# oresat-camera-card-v0.net
KiCad netlist of a schematic drawn in EAGLE
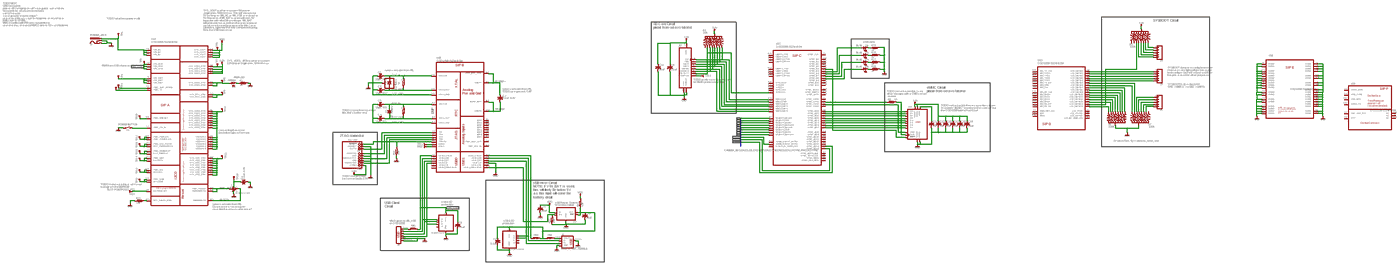
[diagram p0: schematic, sheet 1, overview]
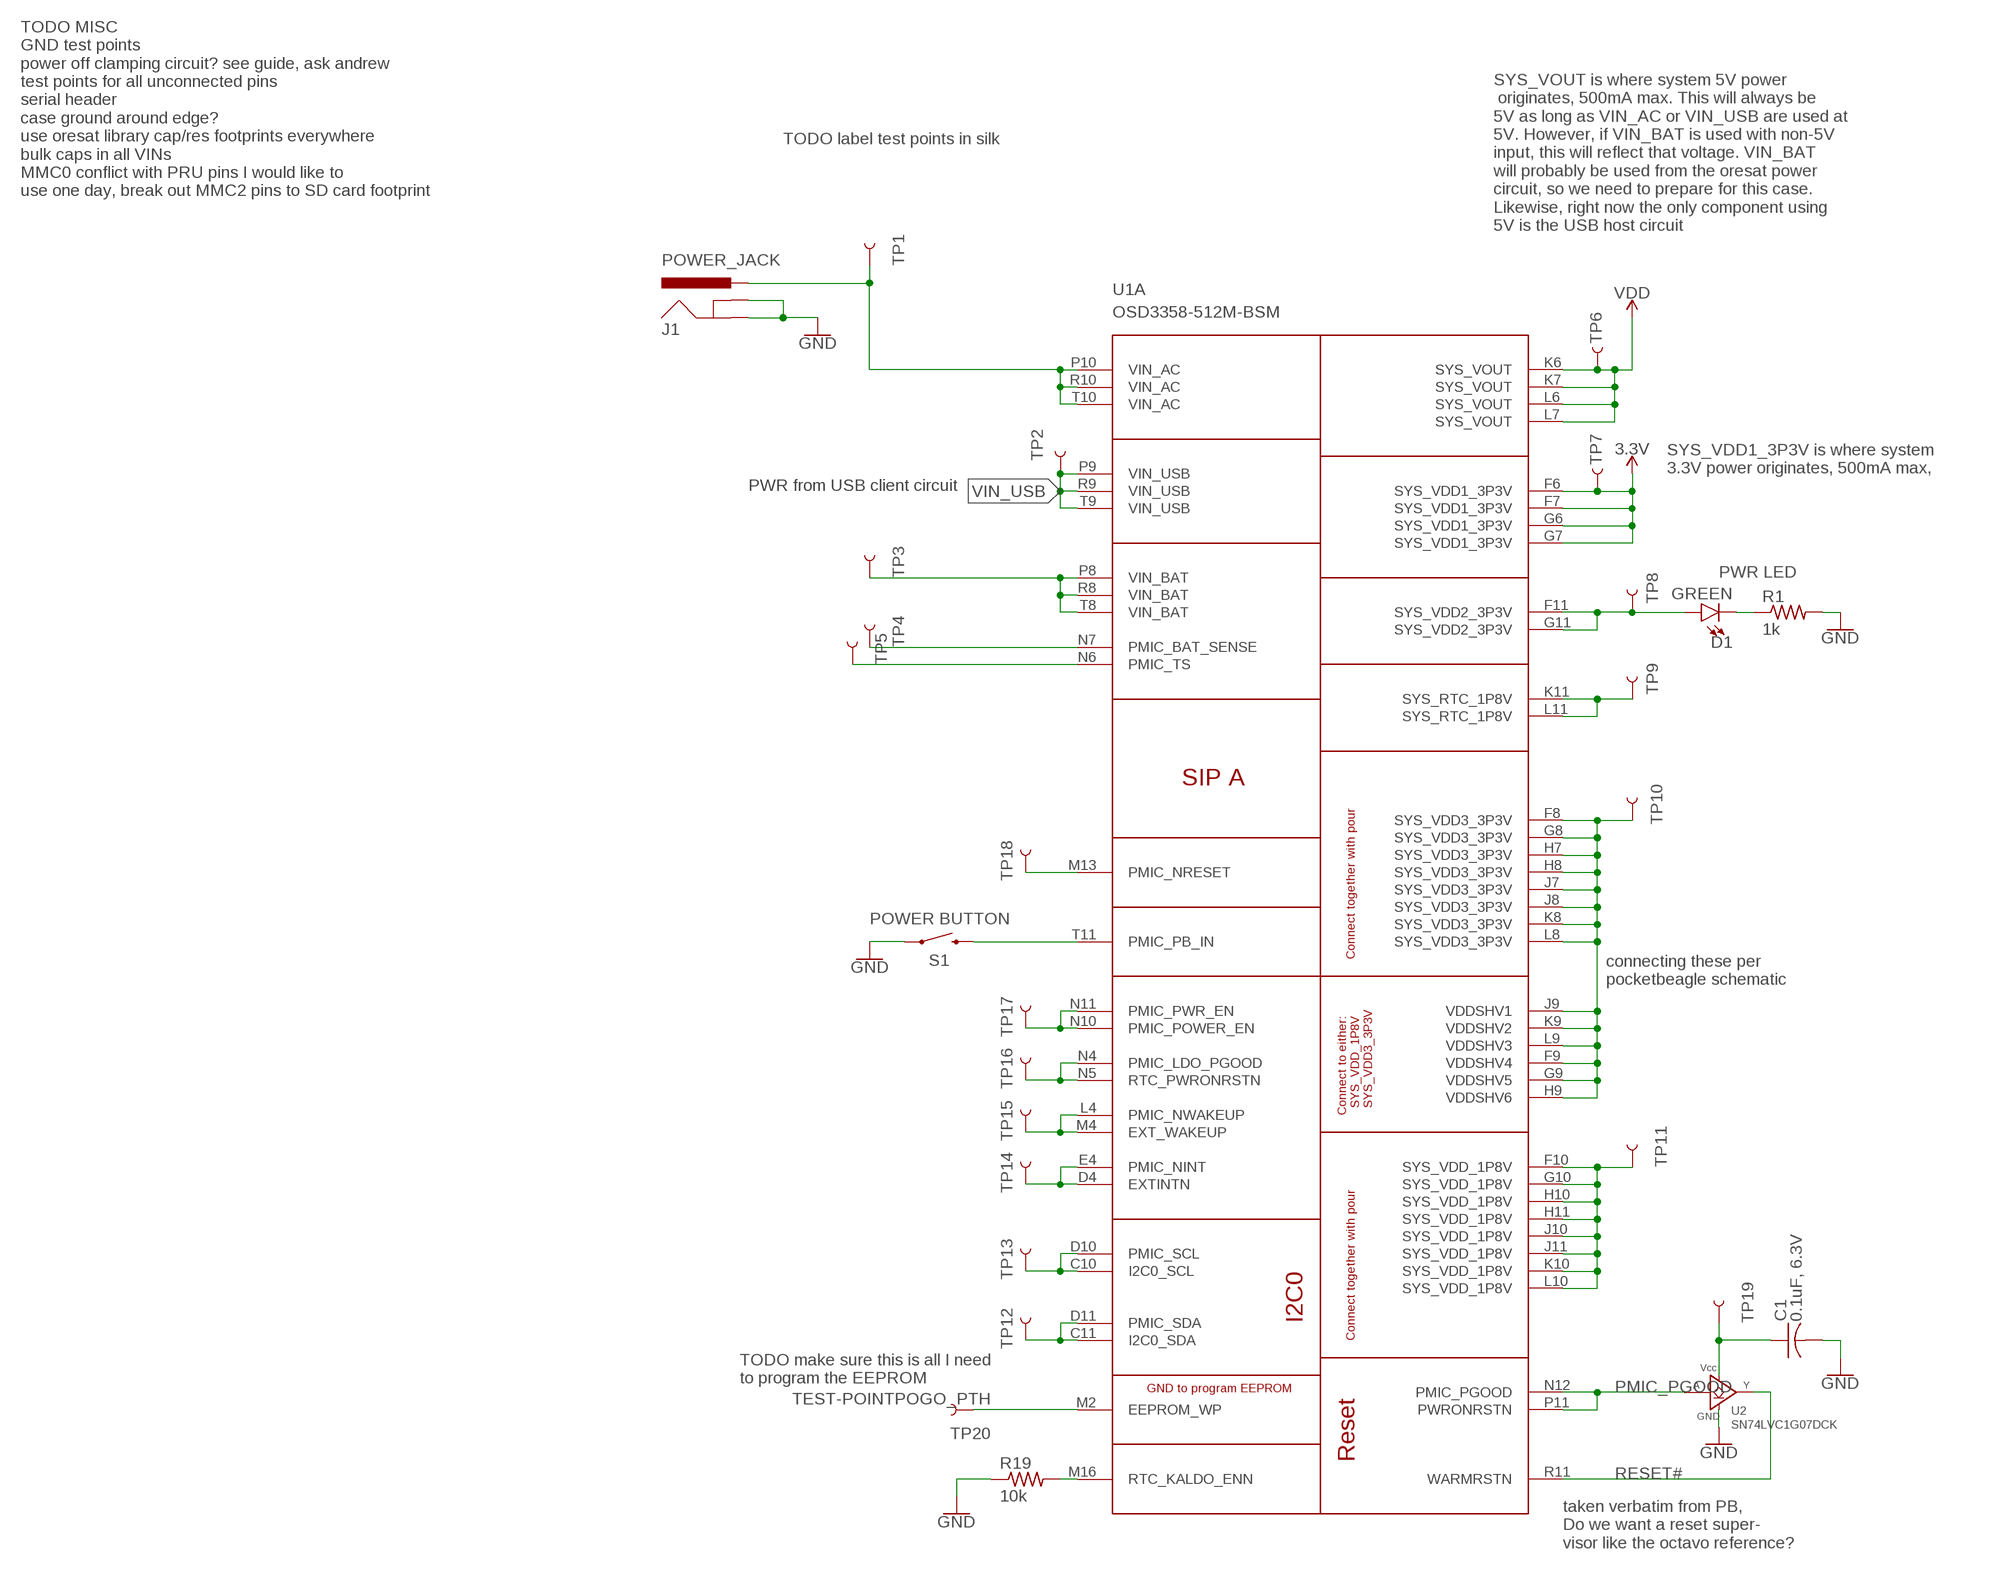
[diagram p1: schematic, sheet 1, part 1 of 4]
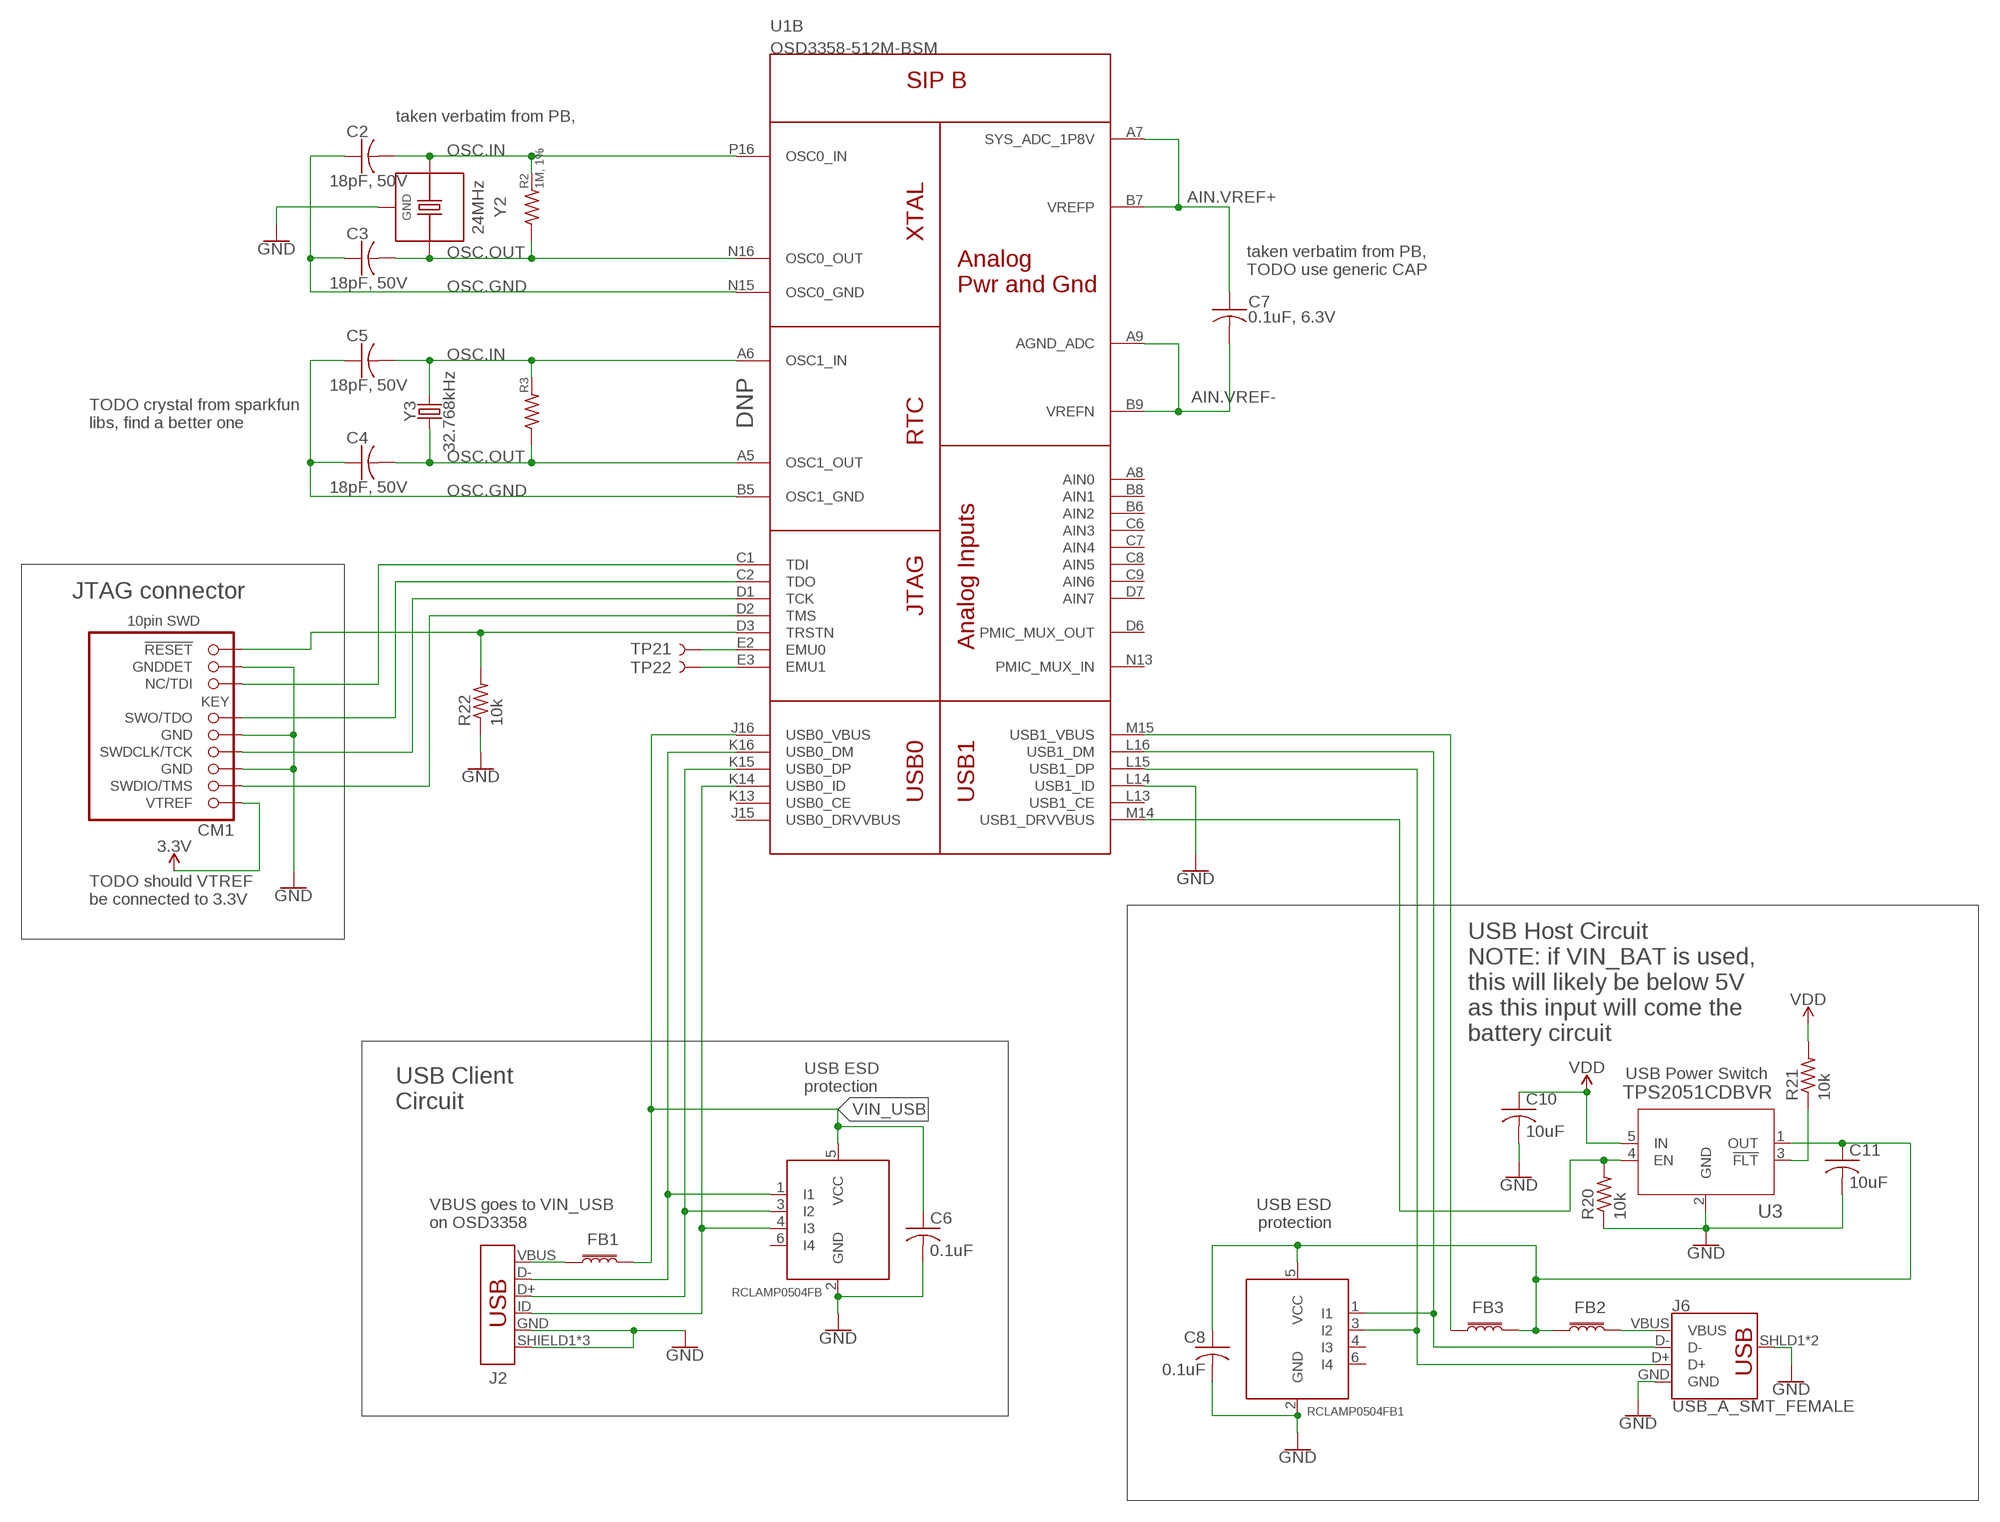
[diagram p2: schematic, sheet 1, part 2 of 4]
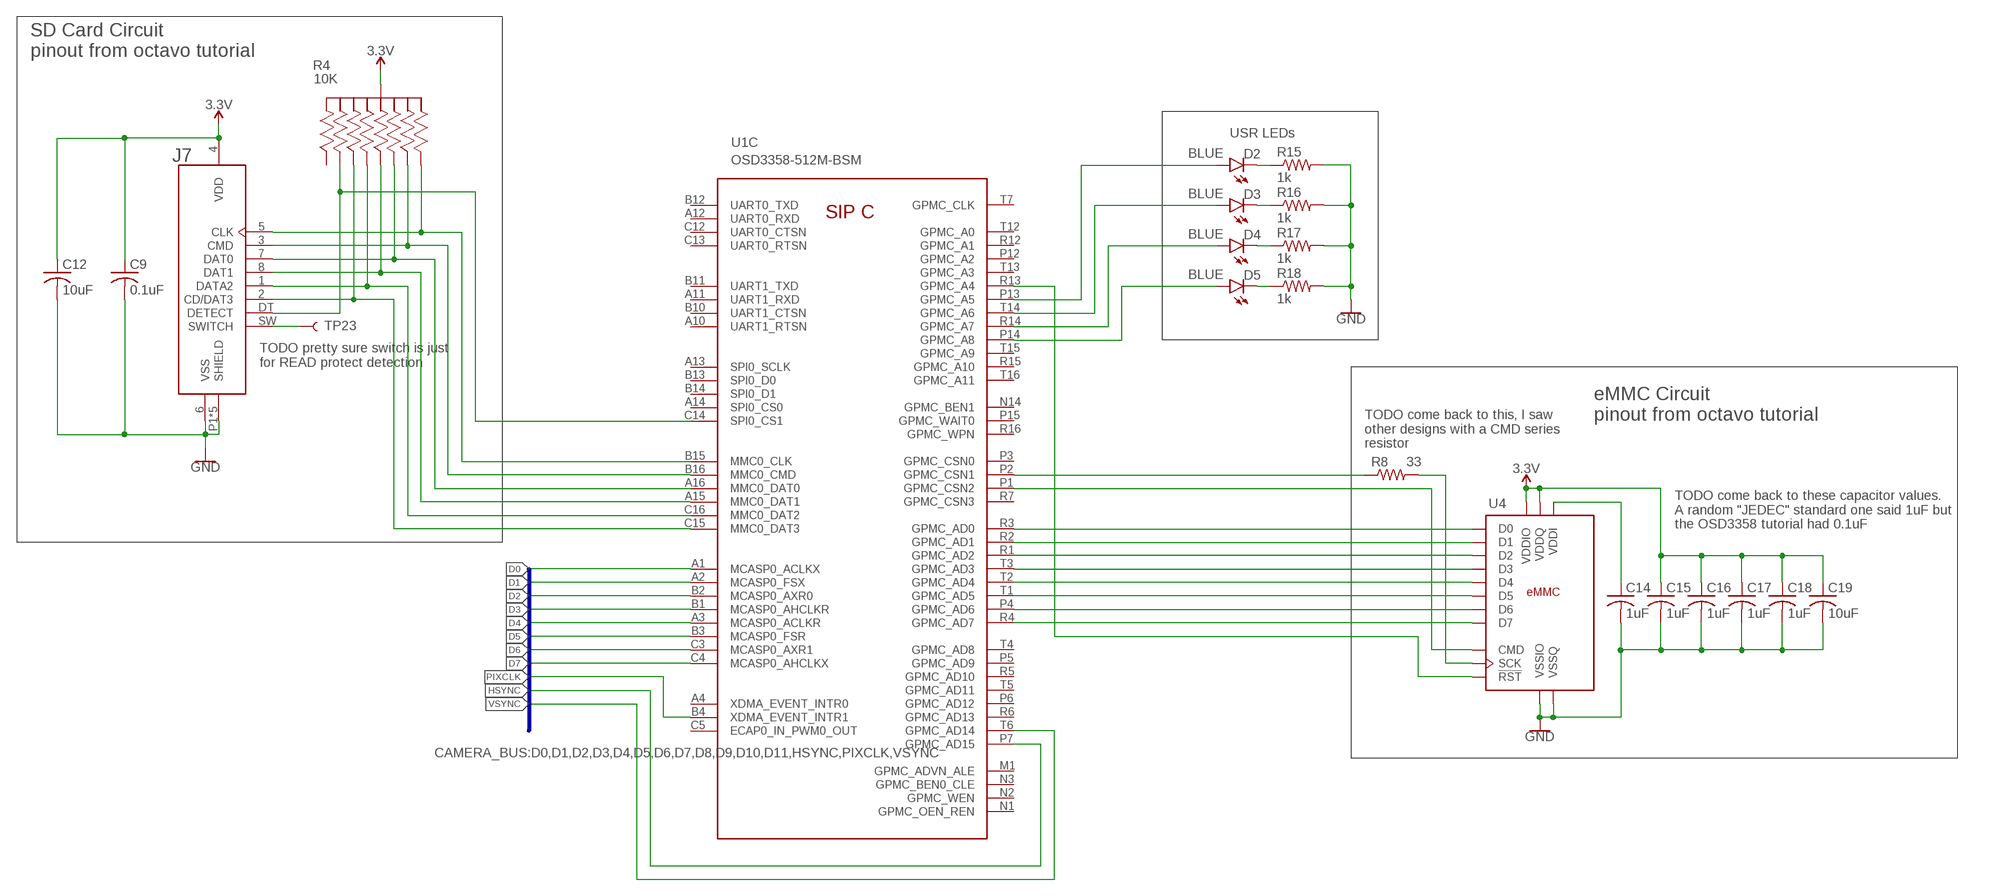
[diagram p3: schematic, sheet 1, part 3 of 4]
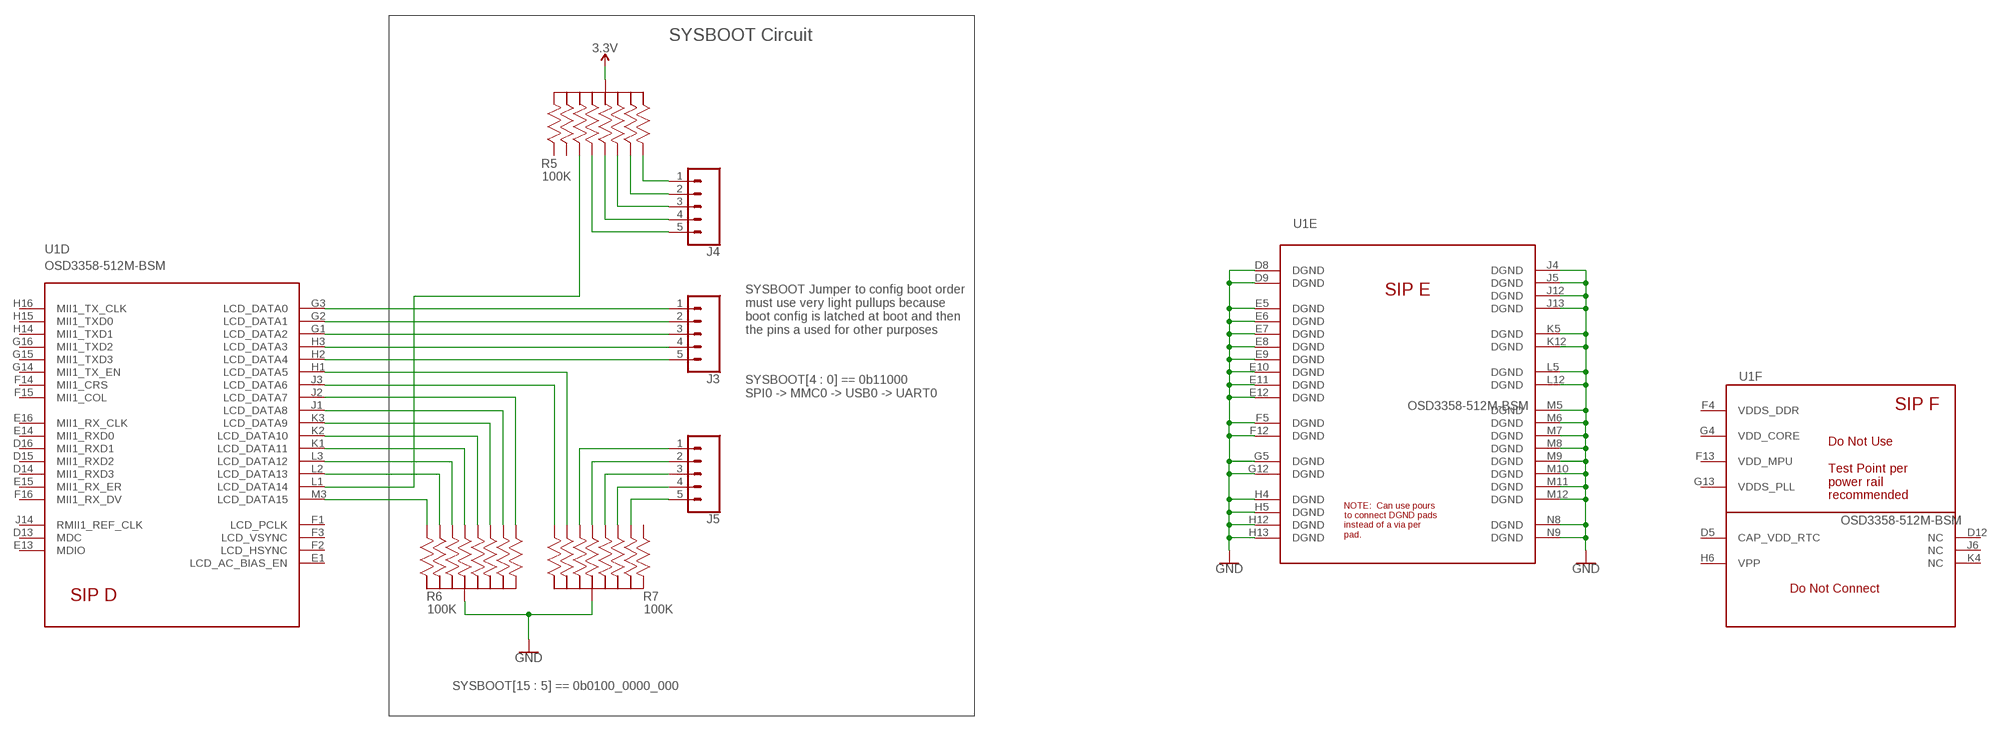
[diagram p4: schematic, sheet 1, part 4 of 4]

(export (version "E")
  (design (tool "Eeschema 10.0.6"))
  (components
    (comp (ref "C1")
      (value "0.1uF, 6.3V")
      (footprint "eagle-import:C0603")
      (libsource (lib "eagle-import") (part "C-USC0603"))
    )
    (comp (ref "C2")
      (value "18pF, 50V")
      (footprint "eagle-import:C0603")
      (libsource (lib "eagle-import") (part "C-USC0603"))
    )
    (comp (ref "C3")
      (value "18pF, 50V")
      (footprint "eagle-import:C0603")
      (libsource (lib "eagle-import") (part "C-USC0603"))
    )
    (comp (ref "C4")
      (value "18pF, 50V")
      (footprint "eagle-import:C0603")
      (libsource (lib "eagle-import") (part "C-USC0603"))
    )
    (comp (ref "C5")
      (value "18pF, 50V")
      (footprint "eagle-import:C0603")
      (libsource (lib "eagle-import") (part "C-USC0603"))
    )
    (comp (ref "C6")
      (value "0.1uF")
      (footprint "eagle-import:C0603")
      (libsource (lib "eagle-import") (part "C-USC0603"))
    )
    (comp (ref "C7")
      (value "0.1uF, 6.3V")
      (footprint "eagle-import:C0603")
      (libsource (lib "eagle-import") (part "C-USC0603"))
    )
    (comp (ref "C8")
      (value "0.1uF")
      (footprint "eagle-import:C0603")
      (libsource (lib "eagle-import") (part "C-USC0603"))
    )
    (comp (ref "C9")
      (value "0.1uF")
      (footprint "eagle-import:C0603")
      (libsource (lib "eagle-import") (part "C-USC0603"))
    )
    (comp (ref "C10")
      (value "10uF")
      (footprint "eagle-import:C0603")
      (libsource (lib "eagle-import") (part "C-USC0603"))
    )
    (comp (ref "C11")
      (value "10uF")
      (footprint "eagle-import:C0603")
      (libsource (lib "eagle-import") (part "C-USC0603"))
    )
    (comp (ref "C12")
      (value "10uF")
      (footprint "eagle-import:C0603")
      (libsource (lib "eagle-import") (part "C-USC0603"))
    )
    (comp (ref "C14")
      (value "1uF")
      (footprint "eagle-import:C0603")
      (libsource (lib "eagle-import") (part "C-USC0603"))
    )
    (comp (ref "C15")
      (value "1uF")
      (footprint "eagle-import:C0603")
      (libsource (lib "eagle-import") (part "C-USC0603"))
    )
    (comp (ref "C16")
      (value "1uF")
      (footprint "eagle-import:C0603")
      (libsource (lib "eagle-import") (part "C-USC0603"))
    )
    (comp (ref "C17")
      (value "1uF")
      (footprint "eagle-import:C0603")
      (libsource (lib "eagle-import") (part "C-USC0603"))
    )
    (comp (ref "C18")
      (value "1uF")
      (footprint "eagle-import:C0603")
      (libsource (lib "eagle-import") (part "C-USC0603"))
    )
    (comp (ref "C19")
      (value "10uF")
      (footprint "eagle-import:C0603")
      (libsource (lib "eagle-import") (part "C-USC0603"))
    )
    (comp (ref "CM1")
      (value "FTSH-105-XX-X-DV-K")
      (footprint "eagle-import:CON10_2X5_DUK_FTSH")
      (libsource (lib "eagle-import") (part "FTSH-105-XX-X-DV-K"))
    )
    (comp (ref "D1")
      (value "GREEN")
      (footprint "eagle-import:LED-0603")
      (libsource (lib "eagle-import") (part "LED-GREEN0603"))
    )
    (comp (ref "D2")
      (value "BLUE")
      (footprint "eagle-import:LED-0603")
      (libsource (lib "eagle-import") (part "LED-BLUE0603"))
    )
    (comp (ref "D3")
      (value "BLUE")
      (footprint "eagle-import:LED-0603")
      (libsource (lib "eagle-import") (part "LED-BLUE0603"))
    )
    (comp (ref "D4")
      (value "BLUE")
      (footprint "eagle-import:LED-0603")
      (libsource (lib "eagle-import") (part "LED-BLUE0603"))
    )
    (comp (ref "D5")
      (value "BLUE")
      (footprint "eagle-import:LED-0603")
      (libsource (lib "eagle-import") (part "LED-BLUE0603"))
    )
    (comp (ref "FB1")
      (value "30Ω/1.8A")
      (footprint "eagle-import:0603")
      (libsource (lib "eagle-import") (part "FERRITE_BEAD-0603"))
    )
    (comp (ref "FB2")
      (value "30Ω/1.8A")
      (footprint "eagle-import:0603")
      (libsource (lib "eagle-import") (part "FERRITE_BEAD-0603"))
    )
    (comp (ref "FB3")
      (value "30Ω/1.8A")
      (footprint "eagle-import:0603")
      (libsource (lib "eagle-import") (part "FERRITE_BEAD-0603"))
    )
    (comp (ref "J1")
      (value "POWER_JACK")
      (footprint "eagle-import:POWER_JACK_PTH")
      (libsource (lib "eagle-import") (part "POWER_JACK"))
    )
    (comp (ref "J2")
      (value "USB_MICRO-B_FEMALE-SMT")
      (footprint "eagle-import:USB-B-MICRO-SMD")
      (libsource (lib "eagle-import") (part "USB_MICRO-B_FEMALE-SMT"))
    )
    (comp (ref "J3")
      (value "CONN_05")
      (footprint "eagle-import:1X05")
      (libsource (lib "eagle-import") (part "CONN_05"))
    )
    (comp (ref "J4")
      (value "CONN_05")
      (footprint "eagle-import:1X05")
      (libsource (lib "eagle-import") (part "CONN_05"))
    )
    (comp (ref "J5")
      (value "CONN_05")
      (footprint "eagle-import:1X05")
      (libsource (lib "eagle-import") (part "CONN_05"))
    )
    (comp (ref "J6")
      (value "USB_A_SMT_FEMALE")
      (footprint "eagle-import:USB-A-S-SILK-FEMALE")
      (libsource (lib "eagle-import") (part "USB_A_SMT_FEMALE"))
    )
    (comp (ref "J7")
      (value "503182-1852")
      (footprint "eagle-import:MOLEX_503182-1852")
      (fields
        (field (name "DIGI-KEY_PART_NUMBER") "WM12834CT-ND")
        (field (name "MF") "Molex")
        (field (name "MP") "5031821852")
      )
      (libsource (lib "eagle-import") (part "503182-1852"))
    )
    (comp (ref "R1")
      (value "1k")
      (footprint "eagle-import:.0603-A")
      (libsource (lib "eagle-import") (part "R-US_0603-A"))
    )
    (comp (ref "R2")
      (value "1M, 1%")
      (footprint "eagle-import:.0603-A")
      (libsource (lib "eagle-import") (part "R-US_0603-A"))
    )
    (comp (ref "R3")
      (value "1M, 1%")
      (footprint "eagle-import:.0603-A")
      (libsource (lib "eagle-import") (part "R-US_0603-A"))
    )
    (comp (ref "R4")
      (value "10K")
      (footprint "eagle-import:ARRAY_EXBA-M")
      (fields (field (name "MANUFACTURER_PART_NUMBER") "EXBA10P391J"))
      (libsource (lib "eagle-import") (part "EXB-A10P391JC_ARRAY_EXBA-M"))
    )
    (comp (ref "R5")
      (value "100K")
      (footprint "eagle-import:ARRAY_EXBA-M")
      (fields (field (name "MANUFACTURER_PART_NUMBER") "EXBA10P391J"))
      (libsource (lib "eagle-import") (part "EXB-A10P391JC_ARRAY_EXBA-M"))
    )
    (comp (ref "R6")
      (value "100K")
      (footprint "eagle-import:ARRAY_EXBA-M")
      (fields (field (name "MANUFACTURER_PART_NUMBER") "EXBA10P391J"))
      (libsource (lib "eagle-import") (part "EXB-A10P391JC_ARRAY_EXBA-M"))
    )
    (comp (ref "R7")
      (value "100K")
      (footprint "eagle-import:ARRAY_EXBA-M")
      (fields (field (name "MANUFACTURER_PART_NUMBER") "EXBA10P391J"))
      (libsource (lib "eagle-import") (part "EXB-A10P391JC_ARRAY_EXBA-M"))
    )
    (comp (ref "R8")
      (value "33")
      (footprint "eagle-import:.0603-A")
      (libsource (lib "eagle-import") (part "R-US_0603-A"))
    )
    (comp (ref "R15")
      (value "1k")
      (footprint "eagle-import:.0603-A")
      (libsource (lib "eagle-import") (part "R-US_0603-A"))
    )
    (comp (ref "R16")
      (value "1k")
      (footprint "eagle-import:.0603-A")
      (libsource (lib "eagle-import") (part "R-US_0603-A"))
    )
    (comp (ref "R17")
      (value "1k")
      (footprint "eagle-import:.0603-A")
      (libsource (lib "eagle-import") (part "R-US_0603-A"))
    )
    (comp (ref "R18")
      (value "1k")
      (footprint "eagle-import:.0603-A")
      (libsource (lib "eagle-import") (part "R-US_0603-A"))
    )
    (comp (ref "R19")
      (value "10k")
      (footprint "eagle-import:.0603-A")
      (libsource (lib "eagle-import") (part "R-US_0603-A"))
    )
    (comp (ref "R20")
      (value "10k")
      (footprint "eagle-import:.0603-A")
      (libsource (lib "eagle-import") (part "R-US_0603-A"))
    )
    (comp (ref "R21")
      (value "10k")
      (footprint "eagle-import:.0603-A")
      (libsource (lib "eagle-import") (part "R-US_0603-A"))
    )
    (comp (ref "R22")
      (value "10k")
      (footprint "eagle-import:.0603-A")
      (libsource (lib "eagle-import") (part "R-US_0603-A"))
    )
    (comp (ref "RCLAMP0504FB")
      (value "RCLAMP0504FB")
      (footprint "eagle-import:SC70-6")
      (libsource (lib "eagle-import") (part "RCLAMP0504FB"))
    )
    (comp (ref "RCLAMP0504FB1")
      (value "RCLAMP0504FB")
      (footprint "eagle-import:SC70-6")
      (libsource (lib "eagle-import") (part "RCLAMP0504FB"))
    )
    (comp (ref "S1")
      (value "MOMENTARY-SWITCH-SPST-SMD-4.6X2.8MM")
      (footprint "eagle-import:TACTILE_SWITCH_SMD_4.6X2.8MM")
      (libsource (lib "eagle-import") (part "MOMENTARY-SWITCH-SPST-SMD-4.6X2.8MM"))
    )
    (comp (ref "TP1")
      (value "TEST-POINT3X4")
      (footprint "eagle-import:PAD.03X.04")
      (libsource (lib "eagle-import") (part "TEST-POINT3X4"))
    )
    (comp (ref "TP2")
      (value "TEST-POINT3X4")
      (footprint "eagle-import:PAD.03X.04")
      (libsource (lib "eagle-import") (part "TEST-POINT3X4"))
    )
    (comp (ref "TP3")
      (value "TEST-POINT3X4")
      (footprint "eagle-import:PAD.03X.04")
      (libsource (lib "eagle-import") (part "TEST-POINT3X4"))
    )
    (comp (ref "TP4")
      (value "TEST-POINT3X4")
      (footprint "eagle-import:PAD.03X.04")
      (libsource (lib "eagle-import") (part "TEST-POINT3X4"))
    )
    (comp (ref "TP5")
      (value "TEST-POINT3X4")
      (footprint "eagle-import:PAD.03X.04")
      (libsource (lib "eagle-import") (part "TEST-POINT3X4"))
    )
    (comp (ref "TP6")
      (value "TEST-POINT3X4")
      (footprint "eagle-import:PAD.03X.04")
      (libsource (lib "eagle-import") (part "TEST-POINT3X4"))
    )
    (comp (ref "TP7")
      (value "TEST-POINT3X4")
      (footprint "eagle-import:PAD.03X.04")
      (libsource (lib "eagle-import") (part "TEST-POINT3X4"))
    )
    (comp (ref "TP8")
      (value "TEST-POINT3X4")
      (footprint "eagle-import:PAD.03X.04")
      (libsource (lib "eagle-import") (part "TEST-POINT3X4"))
    )
    (comp (ref "TP9")
      (value "TEST-POINT3X4")
      (footprint "eagle-import:PAD.03X.04")
      (libsource (lib "eagle-import") (part "TEST-POINT3X4"))
    )
    (comp (ref "TP10")
      (value "TEST-POINT3X4")
      (footprint "eagle-import:PAD.03X.04")
      (libsource (lib "eagle-import") (part "TEST-POINT3X4"))
    )
    (comp (ref "TP11")
      (value "TEST-POINT3X4")
      (footprint "eagle-import:PAD.03X.04")
      (libsource (lib "eagle-import") (part "TEST-POINT3X4"))
    )
    (comp (ref "TP12")
      (value "TEST-POINT3X4")
      (footprint "eagle-import:PAD.03X.04")
      (libsource (lib "eagle-import") (part "TEST-POINT3X4"))
    )
    (comp (ref "TP13")
      (value "TEST-POINT3X4")
      (footprint "eagle-import:PAD.03X.04")
      (libsource (lib "eagle-import") (part "TEST-POINT3X4"))
    )
    (comp (ref "TP14")
      (value "TEST-POINT3X4")
      (footprint "eagle-import:PAD.03X.04")
      (libsource (lib "eagle-import") (part "TEST-POINT3X4"))
    )
    (comp (ref "TP15")
      (value "TEST-POINT3X4")
      (footprint "eagle-import:PAD.03X.04")
      (libsource (lib "eagle-import") (part "TEST-POINT3X4"))
    )
    (comp (ref "TP16")
      (value "TEST-POINT3X4")
      (footprint "eagle-import:PAD.03X.04")
      (libsource (lib "eagle-import") (part "TEST-POINT3X4"))
    )
    (comp (ref "TP17")
      (value "TEST-POINT3X4")
      (footprint "eagle-import:PAD.03X.04")
      (libsource (lib "eagle-import") (part "TEST-POINT3X4"))
    )
    (comp (ref "TP18")
      (value "TEST-POINT3X4")
      (footprint "eagle-import:PAD.03X.04")
      (libsource (lib "eagle-import") (part "TEST-POINT3X4"))
    )
    (comp (ref "TP19")
      (value "TEST-POINT3X4")
      (footprint "eagle-import:PAD.03X.04")
      (libsource (lib "eagle-import") (part "TEST-POINT3X4"))
    )
    (comp (ref "TP20")
      (value "TEST-POINTPOGO_PTH")
      (footprint "eagle-import:1X01_NO_SILK")
      (libsource (lib "eagle-import") (part "TEST-POINTPOGO_PTH"))
    )
    (comp (ref "TP21")
      (value "TEST-POINT3X4")
      (footprint "eagle-import:PAD.03X.04")
      (libsource (lib "eagle-import") (part "TEST-POINT3X4"))
    )
    (comp (ref "TP22")
      (value "TEST-POINT3X4")
      (footprint "eagle-import:PAD.03X.04")
      (libsource (lib "eagle-import") (part "TEST-POINT3X4"))
    )
    (comp (ref "TP23")
      (value "TEST-POINT3X4")
      (footprint "eagle-import:PAD.03X.04")
      (libsource (lib "eagle-import") (part "TEST-POINT3X4"))
    )
    (comp (ref "U1")
      (value "OSD3358-512M-BSM")
      (footprint "eagle-import:OSD335X-BGA-256")
      (fields (field (name "DIGI-KEY_PART_NUMBER") "1676-1002-ND") (field (name "MF") "Octavo Systems"))
      (libsource (lib "eagle-import") (part "OSD3358-512M-BSM"))
    )
    (comp (ref "U2")
      (value "SN74LVC1G07DCK")
      (footprint "eagle-import:SC70(TI-DCK)")
      (libsource (lib "eagle-import") (part "SN74LVC1G07DCK"))
    )
    (comp (ref "U3")
      (value "TPS2051CDBVR")
      (footprint "eagle-import:DBV5")
      (libsource (lib "eagle-import") (part "TPS2051CDBVR"))
    )
    (comp (ref "U4")
      (value "EMMC+RESET-BA")
      (footprint "eagle-import:BGA-153(11.5X13)(EMMC-BA)")
      (libsource (lib "eagle-import") (part "EMMC+RESET-BA"))
    )
    (comp (ref "Y2")
      (value "24MHz")
      (footprint "eagle-import:5X3.2-4SMD")
      (libsource (lib "eagle-import") (part "ECS-240-12-30BQ-AEN-TR"))
    )
    (comp (ref "Y3")
      (value "32.768kHz")
      (footprint "eagle-import:CRYSTAL-SMD-3.2X1.5MM")
      (libsource (lib "eagle-import") (part "CRYSTAL-32.768KHZSMD-3.2X1.5"))
    )
  )
  (nets
    (net (code "6") (name "/AIN.VREF+") (class "Default")
      (node (ref "C7") (pin "1") (pinfunction "1_1") (pintype "passive"))
      (node (ref "U1") (pin "A7") (pinfunction "SYS_ADC_1P8V_A7") (pintype "bidirectional"))
      (node (ref "U1") (pin "B7") (pinfunction "VREFP_B7") (pintype "bidirectional"))
    )
    (net (code "7") (name "/AIN.VREF-") (class "Default")
      (node (ref "C7") (pin "2") (pinfunction "2_2") (pintype "passive"))
      (node (ref "U1") (pin "A9") (pinfunction "AGND_ADC_A9") (pintype "bidirectional"))
      (node (ref "U1") (pin "B9") (pinfunction "VREFN_B9") (pintype "bidirectional"))
    )
    (net (code "8") (name "/OSC.GND") (class "Default")
      (node (ref "C2") (pin "1") (pinfunction "1_1") (pintype "passive"))
      (node (ref "C3") (pin "1") (pinfunction "1_1") (pintype "passive"))
      (node (ref "C4") (pin "1") (pinfunction "1_1") (pintype "passive"))
      (node (ref "C5") (pin "1") (pinfunction "1_1") (pintype "passive"))
      (node (ref "U1") (pin "B5") (pinfunction "OSC1_GND_B5") (pintype "bidirectional"))
      (node (ref "U1") (pin "N15") (pinfunction "OSC0_GND_N15") (pintype "bidirectional"))
    )
    (net (code "9") (name "/OSC.IN") (class "Default")
      (node (ref "C2") (pin "2") (pinfunction "2_2") (pintype "passive"))
      (node (ref "C5") (pin "2") (pinfunction "2_2") (pintype "passive"))
      (node (ref "R2") (pin "2") (pinfunction "2_2") (pintype "passive"))
      (node (ref "R3") (pin "2") (pinfunction "2_2") (pintype "passive"))
      (node (ref "U1") (pin "A6") (pinfunction "OSC1_IN_A6") (pintype "bidirectional"))
      (node (ref "U1") (pin "P16") (pinfunction "OSC0_IN_P16") (pintype "bidirectional"))
      (node (ref "Y2") (pin "1") (pinfunction "X1_1") (pintype "passive"))
      (node (ref "Y3") (pin "P$2") (pinfunction "2_P$2") (pintype "passive"))
    )
    (net (code "10") (name "/OSC.OUT") (class "Default")
      (node (ref "C3") (pin "2") (pinfunction "2_2") (pintype "passive"))
      (node (ref "C4") (pin "2") (pinfunction "2_2") (pintype "passive"))
      (node (ref "R2") (pin "1") (pinfunction "1_1") (pintype "passive"))
      (node (ref "R3") (pin "1") (pinfunction "1_1") (pintype "passive"))
      (node (ref "U1") (pin "A5") (pinfunction "OSC1_OUT_A5") (pintype "bidirectional"))
      (node (ref "U1") (pin "N16") (pinfunction "OSC0_OUT_N16") (pintype "bidirectional"))
      (node (ref "Y2") (pin "3") (pinfunction "X2_3") (pintype "passive"))
      (node (ref "Y3") (pin "P$1") (pinfunction "1_P$1") (pintype "passive"))
    )
    (net (code "11") (name "/PMIC_PGOOD") (class "Default")
      (node (ref "U1") (pin "N12") (pinfunction "PMIC_PGOOD_N12") (pintype "output"))
      (node (ref "U1") (pin "P11") (pinfunction "PWRONRSTN_P11") (pintype "bidirectional"))
      (node (ref "U2") (pin "2") (pinfunction "A_2") (pintype "bidirectional"))
    )
    (net (code "12") (name "/RESET#") (class "Default")
      (node (ref "U1") (pin "R11") (pinfunction "WARMRSTN_R11") (pintype "bidirectional"))
      (node (ref "U2") (pin "4") (pinfunction "Y_4") (pintype "bidirectional"))
    )
    (net (code "14") (name "3.3V") (class "Default")
      (node (ref "C12") (pin "1") (pinfunction "1_1") (pintype "passive"))
      (node (ref "C15") (pin "1") (pinfunction "1_1") (pintype "passive"))
      (node (ref "C16") (pin "1") (pinfunction "1_1") (pintype "passive"))
      (node (ref "C17") (pin "1") (pinfunction "1_1") (pintype "passive"))
      (node (ref "C18") (pin "1") (pinfunction "1_1") (pintype "passive"))
      (node (ref "C19") (pin "1") (pinfunction "1_1") (pintype "passive"))
      (node (ref "C9") (pin "1") (pinfunction "1_1") (pintype "passive"))
      (node (ref "CM1") (pin "1") (pinfunction "VTREF_1") (pintype "passive"))
      (node (ref "J7") (pin "4") (pinfunction "VDD_4") (pintype "power_in"))
      (node (ref "R4") (pin "10") (pinfunction "55_10") (pintype "passive"))
      (node (ref "R4") (pin "5") (pinfunction "55_5") (pintype "passive"))
      (node (ref "R5") (pin "10") (pinfunction "55_10") (pintype "passive"))
      (node (ref "R5") (pin "5") (pinfunction "55_5") (pintype "passive"))
      (node (ref "TP7") (pin "P$1") (pinfunction "1_P$1") (pintype "bidirectional"))
      (node (ref "U1") (pin "F6") (pinfunction "SYS_VDD1_3P3V_F6") (pintype "power_in"))
      (node (ref "U1") (pin "F7") (pinfunction "SYS_VDD1_3P3V_F7") (pintype "power_in"))
      (node (ref "U1") (pin "G6") (pinfunction "SYS_VDD1_3P3V_G6") (pintype "power_in"))
      (node (ref "U1") (pin "G7") (pinfunction "SYS_VDD1_3P3V_G7") (pintype "power_in"))
      (node (ref "U4") (pin "C6") (pinfunction "VDDQ_C6") (pintype "power_in"))
      (node (ref "U4") (pin "E6") (pinfunction "VDDIO_E6") (pintype "power_in"))
      (node (ref "U4") (pin "F5") (pinfunction "VDDIO_F5") (pintype "power_in"))
      (node (ref "U4") (pin "J10") (pinfunction "VDDIO_J10") (pintype "power_in"))
      (node (ref "U4") (pin "K9") (pinfunction "VDDIO_K9") (pintype "power_in"))
      (node (ref "U4") (pin "M4") (pinfunction "VDDQ_M4") (pintype "power_in"))
      (node (ref "U4") (pin "N4") (pinfunction "VDDQ_N4") (pintype "power_in"))
      (node (ref "U4") (pin "P3") (pinfunction "VDDQ_P3") (pintype "power_in"))
      (node (ref "U4") (pin "P5") (pinfunction "VDDQ_P5") (pintype "power_in"))
    )
    (net (code "15") (name "D0") (class "Default")
      (node (ref "U1") (pin "A1") (pinfunction "MCASP0_ACLKX_A1") (pintype "bidirectional"))
    )
    (net (code "16") (name "D1") (class "Default")
      (node (ref "U1") (pin "A2") (pinfunction "MCASP0_FSX_A2") (pintype "bidirectional"))
    )
    (net (code "17") (name "D2") (class "Default")
      (node (ref "U1") (pin "B2") (pinfunction "MCASP0_AXR0_B2") (pintype "bidirectional"))
    )
    (net (code "18") (name "D3") (class "Default")
      (node (ref "U1") (pin "B1") (pinfunction "MCASP0_AHCLKR_B1") (pintype "bidirectional"))
    )
    (net (code "19") (name "D4") (class "Default")
      (node (ref "U1") (pin "A3") (pinfunction "MCASP0_ACLKR_A3") (pintype "bidirectional"))
    )
    (net (code "20") (name "D5") (class "Default")
      (node (ref "U1") (pin "B3") (pinfunction "MCASP0_FSR_B3") (pintype "bidirectional"))
    )
    (net (code "21") (name "D6") (class "Default")
      (node (ref "U1") (pin "C3") (pinfunction "MCASP0_AXR1_C3") (pintype "bidirectional"))
    )
    (net (code "22") (name "D7") (class "Default")
      (node (ref "U1") (pin "C4") (pinfunction "MCASP0_AHCLKX_C4") (pintype "bidirectional"))
    )
    (net (code "23") (name "GND") (class "Default")
      (node (ref "C1") (pin "2") (pinfunction "2_2") (pintype "passive"))
      (node (ref "C10") (pin "2") (pinfunction "2_2") (pintype "passive"))
      (node (ref "C11") (pin "2") (pinfunction "2_2") (pintype "passive"))
      (node (ref "C12") (pin "2") (pinfunction "2_2") (pintype "passive"))
      (node (ref "C14") (pin "2") (pinfunction "2_2") (pintype "passive"))
      (node (ref "C15") (pin "2") (pinfunction "2_2") (pintype "passive"))
      (node (ref "C16") (pin "2") (pinfunction "2_2") (pintype "passive"))
      (node (ref "C17") (pin "2") (pinfunction "2_2") (pintype "passive"))
      (node (ref "C18") (pin "2") (pinfunction "2_2") (pintype "passive"))
      (node (ref "C19") (pin "2") (pinfunction "2_2") (pintype "passive"))
      (node (ref "C6") (pin "2") (pinfunction "2_2") (pintype "passive"))
      (node (ref "C8") (pin "2") (pinfunction "2_2") (pintype "passive"))
      (node (ref "C9") (pin "2") (pinfunction "2_2") (pintype "passive"))
      (node (ref "CM1") (pin "3") (pinfunction "GND_3") (pintype "passive"))
      (node (ref "CM1") (pin "5") (pinfunction "GND_5") (pintype "passive"))
      (node (ref "CM1") (pin "9") (pinfunction "GNDDET_9") (pintype "passive"))
      (node (ref "J1") (pin "GND") (pinfunction "GND_GND") (pintype "bidirectional"))
      (node (ref "J1") (pin "GNDBREAK") (pinfunction "GNDBREAK_GNDBREAK") (pintype "bidirectional"))
      (node (ref "J2") (pin "GND") (pinfunction "GND_GND") (pintype "power_in"))
      (node (ref "J2") (pin "SHIELD1") (pinfunction "SHIELD_SHIELD1") (pintype "bidirectional"))
      (node (ref "J2") (pin "SHIELD2") (pinfunction "SHIELD_SHIELD2") (pintype "bidirectional"))
      (node (ref "J2") (pin "SHIELD3") (pinfunction "SHIELD_SHIELD3") (pintype "bidirectional"))
      (node (ref "J6") (pin "GND") (pinfunction "GND_GND") (pintype "power_in"))
      (node (ref "J6") (pin "SHLD1") (pinfunction "SHIELD_SHLD1") (pintype "bidirectional"))
      (node (ref "J6") (pin "SHLD2") (pinfunction "SHIELD_SHLD2") (pintype "bidirectional"))
      (node (ref "J7") (pin "6") (pinfunction "VSS_6") (pintype "power_in"))
      (node (ref "J7") (pin "P1") (pinfunction "SHIELD_P1") (pintype "passive"))
      (node (ref "J7") (pin "P2") (pinfunction "SHIELD_P2") (pintype "passive"))
      (node (ref "J7") (pin "P3") (pinfunction "SHIELD_P3") (pintype "passive"))
      (node (ref "J7") (pin "P4") (pinfunction "SHIELD_P4") (pintype "passive"))
      (node (ref "J7") (pin "P5") (pinfunction "SHIELD_P5") (pintype "passive"))
      (node (ref "R1") (pin "2") (pinfunction "2_2") (pintype "passive"))
      (node (ref "R15") (pin "2") (pinfunction "2_2") (pintype "passive"))
      (node (ref "R16") (pin "2") (pinfunction "2_2") (pintype "passive"))
      (node (ref "R17") (pin "2") (pinfunction "2_2") (pintype "passive"))
      (node (ref "R18") (pin "2") (pinfunction "2_2") (pintype "passive"))
      (node (ref "R19") (pin "1") (pinfunction "1_1") (pintype "passive"))
      (node (ref "R20") (pin "1") (pinfunction "1_1") (pintype "passive"))
      (node (ref "R22") (pin "1") (pinfunction "1_1") (pintype "passive"))
      (node (ref "R6") (pin "10") (pinfunction "55_10") (pintype "passive"))
      (node (ref "R6") (pin "5") (pinfunction "55_5") (pintype "passive"))
      (node (ref "R7") (pin "10") (pinfunction "55_10") (pintype "passive"))
      (node (ref "R7") (pin "5") (pinfunction "55_5") (pintype "passive"))
      (node (ref "RCLAMP0504FB") (pin "2") (pinfunction "GND_2") (pintype "power_in"))
      (node (ref "RCLAMP0504FB1") (pin "2") (pinfunction "GND_2") (pintype "power_in"))
      (node (ref "S1") (pin "1") (pinfunction "1_1") (pintype "passive"))
      (node (ref "S1") (pin "2") (pinfunction "1_2") (pintype "passive"))
      (node (ref "U1") (pin "D8") (pinfunction "DGND_D8") (pintype "bidirectional"))
      (node (ref "U1") (pin "D9") (pinfunction "DGND_D9") (pintype "bidirectional"))
      (node (ref "U1") (pin "E10") (pinfunction "DGND_E10") (pintype "bidirectional"))
      (node (ref "U1") (pin "E11") (pinfunction "DGND_E11") (pintype "bidirectional"))
      (node (ref "U1") (pin "E12") (pinfunction "DGND_E12") (pintype "bidirectional"))
      (node (ref "U1") (pin "E5") (pinfunction "DGND_E5") (pintype "bidirectional"))
      (node (ref "U1") (pin "E6") (pinfunction "DGND_E6") (pintype "bidirectional"))
      (node (ref "U1") (pin "E7") (pinfunction "DGND_E7") (pintype "bidirectional"))
      (node (ref "U1") (pin "E8") (pinfunction "DGND_E8") (pintype "bidirectional"))
      (node (ref "U1") (pin "E9") (pinfunction "DGND_E9") (pintype "bidirectional"))
      (node (ref "U1") (pin "F12") (pinfunction "DGND_F12") (pintype "bidirectional"))
      (node (ref "U1") (pin "F5") (pinfunction "DGND_F5") (pintype "bidirectional"))
      (node (ref "U1") (pin "G12") (pinfunction "DGND_G12") (pintype "bidirectional"))
      (node (ref "U1") (pin "G5") (pinfunction "DGND_G5") (pintype "bidirectional"))
      (node (ref "U1") (pin "H12") (pinfunction "DGND_H12") (pintype "bidirectional"))
      (node (ref "U1") (pin "H13") (pinfunction "DGND_H13") (pintype "bidirectional"))
      (node (ref "U1") (pin "H4") (pinfunction "DGND_H4") (pintype "bidirectional"))
      (node (ref "U1") (pin "H5") (pinfunction "DGND_H5") (pintype "bidirectional"))
      (node (ref "U1") (pin "J12") (pinfunction "DGND_J12") (pintype "bidirectional"))
      (node (ref "U1") (pin "J13") (pinfunction "DGND_J13") (pintype "bidirectional"))
      (node (ref "U1") (pin "J4") (pinfunction "DGND_J4") (pintype "bidirectional"))
      (node (ref "U1") (pin "J5") (pinfunction "DGND_J5") (pintype "bidirectional"))
      (node (ref "U1") (pin "K12") (pinfunction "DGND_K12") (pintype "bidirectional"))
      (node (ref "U1") (pin "K5") (pinfunction "DGND_K5") (pintype "bidirectional"))
      (node (ref "U1") (pin "L12") (pinfunction "DGND_L12") (pintype "bidirectional"))
      (node (ref "U1") (pin "L14") (pinfunction "USB1_ID_L14") (pintype "bidirectional"))
      (node (ref "U1") (pin "L5") (pinfunction "DGND_L5") (pintype "bidirectional"))
      (node (ref "U1") (pin "M10") (pinfunction "DGND_M10") (pintype "bidirectional"))
      (node (ref "U1") (pin "M11") (pinfunction "DGND_M11") (pintype "bidirectional"))
      (node (ref "U1") (pin "M12") (pinfunction "DGND_M12") (pintype "bidirectional"))
      (node (ref "U1") (pin "M5") (pinfunction "DGND_M5") (pintype "bidirectional"))
      (node (ref "U1") (pin "M6") (pinfunction "DGND_M6") (pintype "bidirectional"))
      (node (ref "U1") (pin "M7") (pinfunction "DGND_M7") (pintype "bidirectional"))
      (node (ref "U1") (pin "M8") (pinfunction "DGND_M8") (pintype "bidirectional"))
      (node (ref "U1") (pin "M9") (pinfunction "DGND_M9") (pintype "bidirectional"))
      (node (ref "U1") (pin "N8") (pinfunction "DGND_N8") (pintype "bidirectional"))
      (node (ref "U1") (pin "N9") (pinfunction "DGND_N9") (pintype "bidirectional"))
      (node (ref "U2") (pin "3") (pinfunction "GND_3") (pintype "bidirectional"))
      (node (ref "U3") (pin "2") (pinfunction "GND_2") (pintype "power_in"))
      (node (ref "U4") (pin "C4") (pinfunction "VSSQ_C4") (pintype "power_in"))
      (node (ref "U4") (pin "E7") (pinfunction "VSSIO_E7") (pintype "power_in"))
      (node (ref "U4") (pin "G5") (pinfunction "VSSIO_G5") (pintype "power_in"))
      (node (ref "U4") (pin "H10") (pinfunction "VSSIO_H10") (pintype "power_in"))
      (node (ref "U4") (pin "K8") (pinfunction "VSSIO_K8") (pintype "power_in"))
      (node (ref "U4") (pin "N2") (pinfunction "VSSQ_N2") (pintype "power_in"))
      (node (ref "U4") (pin "N5") (pinfunction "VSSQ_N5") (pintype "power_in"))
      (node (ref "U4") (pin "P4") (pinfunction "VSSQ_P4") (pintype "power_in"))
      (node (ref "U4") (pin "P6") (pinfunction "VSSQ_P6") (pintype "power_in"))
      (node (ref "Y2") (pin "2") (pinfunction "GND_2") (pintype "power_in"))
      (node (ref "Y2") (pin "4") (pinfunction "GND_4") (pintype "power_in"))
    )
    (net (code "24") (name "HSYNC") (class "Default")
      (node (ref "U1") (pin "P7") (pinfunction "GPMC_AD15_P7") (pintype "bidirectional"))
    )
    (net (code "25") (name "Net-(CM1-NC{slash}TDI)") (class "Default")
      (node (ref "CM1") (pin "8") (pinfunction "NC/TDI_8") (pintype "passive"))
      (node (ref "U1") (pin "C1") (pinfunction "TDI_C1") (pintype "bidirectional"))
    )
    (net (code "26") (name "Net-(CM1-SWDCLK{slash}TCK)") (class "Default")
      (node (ref "CM1") (pin "4") (pinfunction "SWDCLK/TCK_4") (pintype "passive"))
      (node (ref "U1") (pin "D1") (pinfunction "TCK_D1") (pintype "bidirectional"))
    )
    (net (code "27") (name "Net-(CM1-SWDIO{slash}TMS)") (class "Default")
      (node (ref "CM1") (pin "2") (pinfunction "SWDIO/TMS_2") (pintype "passive"))
      (node (ref "U1") (pin "D2") (pinfunction "TMS_D2") (pintype "bidirectional"))
    )
    (net (code "28") (name "Net-(CM1-SWO{slash}TDO)") (class "Default")
      (node (ref "CM1") (pin "6") (pinfunction "SWO/TDO_6") (pintype "passive"))
      (node (ref "U1") (pin "C2") (pinfunction "TDO_C2") (pintype "bidirectional"))
    )
    (net (code "29") (name "Net-(CM1-~{RESET})") (class "Default")
      (node (ref "CM1") (pin "10") (pinfunction "~{RESET}_10") (pintype "passive"))
      (node (ref "R22") (pin "2") (pinfunction "2_2") (pintype "passive"))
      (node (ref "U1") (pin "D3") (pinfunction "TRSTN_D3") (pintype "bidirectional"))
    )
    (net (code "30") (name "Net-(D1-PadC)") (class "Default")
      (node (ref "D1") (pin "C") (pinfunction "C_C") (pintype "passive"))
      (node (ref "R1") (pin "1") (pinfunction "1_1") (pintype "passive"))
    )
    (net (code "31") (name "Net-(D2-PadC)") (class "Default")
      (node (ref "D2") (pin "C") (pinfunction "C_C") (pintype "passive"))
      (node (ref "R15") (pin "1") (pinfunction "1_1") (pintype "passive"))
    )
    (net (code "32") (name "Net-(D3-PadC)") (class "Default")
      (node (ref "D3") (pin "C") (pinfunction "C_C") (pintype "passive"))
      (node (ref "R16") (pin "1") (pinfunction "1_1") (pintype "passive"))
    )
    (net (code "33") (name "Net-(D4-PadC)") (class "Default")
      (node (ref "D4") (pin "C") (pinfunction "C_C") (pintype "passive"))
      (node (ref "R17") (pin "1") (pinfunction "1_1") (pintype "passive"))
    )
    (net (code "34") (name "Net-(D5-PadC)") (class "Default")
      (node (ref "D5") (pin "C") (pinfunction "C_C") (pintype "passive"))
      (node (ref "R18") (pin "1") (pinfunction "1_1") (pintype "passive"))
    )
    (net (code "35") (name "Net-(FB1-Pad1)") (class "Default")
      (node (ref "FB1") (pin "1") (pinfunction "1_1") (pintype "passive"))
      (node (ref "J2") (pin "VBUS") (pinfunction "VBUS_VBUS") (pintype "power_in"))
    )
    (net (code "36") (name "Net-(FB2-Pad2)") (class "Default")
      (node (ref "FB2") (pin "2") (pinfunction "2_2") (pintype "passive"))
      (node (ref "J6") (pin "VBUS") (pinfunction "VBUS_VBUS") (pintype "power_in"))
    )
    (net (code "37") (name "Net-(J7-CD{slash}DAT3)") (class "Default")
      (node (ref "J7") (pin "2") (pinfunction "CD/DAT3_2") (pintype "bidirectional"))
      (node (ref "R4") (pin "2") (pinfunction "22_2") (pintype "passive"))
      (node (ref "U1") (pin "C15") (pinfunction "MMC0_DAT3_C15") (pintype "bidirectional"))
    )
    (net (code "38") (name "Net-(J7-CLK)") (class "Default")
      (node (ref "J7") (pin "5") (pinfunction "CLK_5") (pintype "bidirectional"))
      (node (ref "R4") (pin "6") (pinfunction "66_6") (pintype "passive"))
      (node (ref "U1") (pin "B15") (pinfunction "MMC0_CLK_B15") (pintype "bidirectional"))
    )
    (net (code "39") (name "Net-(J7-CMD)") (class "Default")
      (node (ref "J7") (pin "3") (pinfunction "CMD_3") (pintype "bidirectional"))
      (node (ref "R4") (pin "4") (pinfunction "44_4") (pintype "passive"))
      (node (ref "U1") (pin "B16") (pinfunction "MMC0_CMD_B16") (pintype "bidirectional"))
    )
    (net (code "40") (name "Net-(J7-DAT0)") (class "Default")
      (node (ref "J7") (pin "7") (pinfunction "DAT0_7") (pintype "bidirectional"))
      (node (ref "R4") (pin "7") (pinfunction "77_7") (pintype "passive"))
      (node (ref "U1") (pin "A16") (pinfunction "MMC0_DAT0_A16") (pintype "bidirectional"))
    )
    (net (code "41") (name "Net-(J7-DAT1)") (class "Default")
      (node (ref "J7") (pin "8") (pinfunction "DAT1_8") (pintype "bidirectional"))
      (node (ref "R4") (pin "3") (pinfunction "33_3") (pintype "passive"))
      (node (ref "U1") (pin "A15") (pinfunction "MMC0_DAT1_A15") (pintype "bidirectional"))
    )
    (net (code "42") (name "Net-(J7-DATA2)") (class "Default")
      (node (ref "J7") (pin "1") (pinfunction "DATA2_1") (pintype "bidirectional"))
      (node (ref "R4") (pin "8") (pinfunction "88_8") (pintype "passive"))
      (node (ref "U1") (pin "C16") (pinfunction "MMC0_DAT2_C16") (pintype "bidirectional"))
    )
    (net (code "43") (name "Net-(J7-DETECT)") (class "Default")
      (node (ref "J7") (pin "DT") (pinfunction "DETECT_DT") (pintype "bidirectional"))
      (node (ref "R4") (pin "9") (pinfunction "99_9") (pintype "passive"))
      (node (ref "U1") (pin "C14") (pinfunction "SPI0_CS1_C14") (pintype "bidirectional"))
    )
    (net (code "44") (name "Net-(J7-SWITCH)") (class "Default")
      (node (ref "J7") (pin "SW") (pinfunction "SWITCH_SW") (pintype "bidirectional"))
      (node (ref "TP23") (pin "P$1") (pinfunction "1_P$1") (pintype "bidirectional"))
    )
    (net (code "45") (name "Net-(R5-22)") (class "Default")
      (node (ref "R5") (pin "2") (pinfunction "22_2") (pintype "passive"))
      (node (ref "U1") (pin "L1") (pinfunction "LCD_DATA14_L1") (pintype "bidirectional"))
    )
    (net (code "46") (name "Net-(R5-33)") (class "Default")
      (node (ref "J4") (pin "4") (pinfunction "4_4") (pintype "passive"))
      (node (ref "R5") (pin "3") (pinfunction "33_3") (pintype "passive"))
    )
    (net (code "47") (name "Net-(R5-44)") (class "Default")
      (node (ref "J4") (pin "2") (pinfunction "2_2") (pintype "passive"))
      (node (ref "R5") (pin "4") (pinfunction "44_4") (pintype "passive"))
    )
    (net (code "48") (name "Net-(R5-66)") (class "Default")
      (node (ref "J4") (pin "1") (pinfunction "1_1") (pintype "passive"))
      (node (ref "R5") (pin "6") (pinfunction "66_6") (pintype "passive"))
    )
    (net (code "49") (name "Net-(R5-77)") (class "Default")
      (node (ref "J4") (pin "3") (pinfunction "3_3") (pintype "passive"))
      (node (ref "R5") (pin "7") (pinfunction "77_7") (pintype "passive"))
    )
    (net (code "50") (name "Net-(R5-88)") (class "Default")
      (node (ref "J4") (pin "5") (pinfunction "5_5") (pintype "passive"))
      (node (ref "R5") (pin "8") (pinfunction "88_8") (pintype "passive"))
    )
    (net (code "51") (name "Net-(R6-11)") (class "Default")
      (node (ref "R6") (pin "1") (pinfunction "11_1") (pintype "passive"))
      (node (ref "U1") (pin "J2") (pinfunction "LCD_DATA7_J2") (pintype "bidirectional"))
    )
    (net (code "52") (name "Net-(R6-22)") (class "Default")
      (node (ref "R6") (pin "2") (pinfunction "22_2") (pintype "passive"))
      (node (ref "U1") (pin "K3") (pinfunction "LCD_DATA9_K3") (pintype "bidirectional"))
    )
    (net (code "53") (name "Net-(R6-33)") (class "Default")
      (node (ref "R6") (pin "3") (pinfunction "33_3") (pintype "passive"))
      (node (ref "U1") (pin "K1") (pinfunction "LCD_DATA11_K1") (pintype "bidirectional"))
    )
    (net (code "54") (name "Net-(R6-44)") (class "Default")
      (node (ref "R6") (pin "4") (pinfunction "44_4") (pintype "passive"))
      (node (ref "U1") (pin "L2") (pinfunction "LCD_DATA13_L2") (pintype "bidirectional"))
    )
    (net (code "55") (name "Net-(R6-66)") (class "Default")
      (node (ref "R6") (pin "6") (pinfunction "66_6") (pintype "passive"))
      (node (ref "U1") (pin "M3") (pinfunction "LCD_DATA15_M3") (pintype "bidirectional"))
    )
    (net (code "56") (name "Net-(R6-77)") (class "Default")
      (node (ref "R6") (pin "7") (pinfunction "77_7") (pintype "passive"))
      (node (ref "U1") (pin "L3") (pinfunction "LCD_DATA12_L3") (pintype "bidirectional"))
    )
    (net (code "57") (name "Net-(R6-88)") (class "Default")
      (node (ref "R6") (pin "8") (pinfunction "88_8") (pintype "passive"))
      (node (ref "U1") (pin "K2") (pinfunction "LCD_DATA10_K2") (pintype "bidirectional"))
    )
    (net (code "58") (name "Net-(R6-99)") (class "Default")
      (node (ref "R6") (pin "9") (pinfunction "99_9") (pintype "passive"))
      (node (ref "U1") (pin "J1") (pinfunction "LCD_DATA8_J1") (pintype "bidirectional"))
    )
    (net (code "59") (name "Net-(R7-22)") (class "Default")
      (node (ref "J5") (pin "4") (pinfunction "4_4") (pintype "passive"))
      (node (ref "R7") (pin "2") (pinfunction "22_2") (pintype "passive"))
    )
    (net (code "60") (name "Net-(R7-33)") (class "Default")
      (node (ref "J5") (pin "2") (pinfunction "2_2") (pintype "passive"))
      (node (ref "R7") (pin "3") (pinfunction "33_3") (pintype "passive"))
    )
    (net (code "61") (name "Net-(R7-44)") (class "Default")
      (node (ref "R7") (pin "4") (pinfunction "44_4") (pintype "passive"))
      (node (ref "U1") (pin "H1") (pinfunction "LCD_DATA5_H1") (pintype "bidirectional"))
    )
    (net (code "62") (name "Net-(R7-66)") (class "Default")
      (node (ref "R7") (pin "6") (pinfunction "66_6") (pintype "passive"))
      (node (ref "U1") (pin "J3") (pinfunction "LCD_DATA6_J3") (pintype "bidirectional"))
    )
    (net (code "63") (name "Net-(R7-77)") (class "Default")
      (node (ref "J5") (pin "1") (pinfunction "1_1") (pintype "passive"))
      (node (ref "R7") (pin "7") (pinfunction "77_7") (pintype "passive"))
    )
    (net (code "64") (name "Net-(R7-88)") (class "Default")
      (node (ref "J5") (pin "3") (pinfunction "3_3") (pintype "passive"))
      (node (ref "R7") (pin "8") (pinfunction "88_8") (pintype "passive"))
    )
    (net (code "65") (name "Net-(R7-99)") (class "Default")
      (node (ref "J5") (pin "5") (pinfunction "5_5") (pintype "passive"))
      (node (ref "R7") (pin "9") (pinfunction "99_9") (pintype "passive"))
    )
    (net (code "66") (name "Net-(RCLAMP0504FB-I1)") (class "Default")
      (node (ref "J2") (pin "D-") (pinfunction "D-_D-") (pintype "bidirectional"))
      (node (ref "RCLAMP0504FB") (pin "1") (pinfunction "I1_1") (pintype "bidirectional"))
      (node (ref "U1") (pin "K16") (pinfunction "USB0_DM_K16") (pintype "bidirectional"))
    )
    (net (code "67") (name "Net-(RCLAMP0504FB-I2)") (class "Default")
      (node (ref "J2") (pin "D+") (pinfunction "D+_D+") (pintype "bidirectional"))
      (node (ref "RCLAMP0504FB") (pin "3") (pinfunction "I2_3") (pintype "bidirectional"))
      (node (ref "U1") (pin "K15") (pinfunction "USB0_DP_K15") (pintype "bidirectional"))
    )
    (net (code "68") (name "Net-(RCLAMP0504FB-I3)") (class "Default")
      (node (ref "J2") (pin "ID") (pinfunction "ID_ID") (pintype "bidirectional"))
      (node (ref "RCLAMP0504FB") (pin "4") (pinfunction "I3_4") (pintype "bidirectional"))
      (node (ref "U1") (pin "K14") (pinfunction "USB0_ID_K14") (pintype "bidirectional"))
    )
    (net (code "69") (name "Net-(RCLAMP0504FB1-I1)") (class "Default")
      (node (ref "J6") (pin "D-") (pinfunction "D-_D-") (pintype "bidirectional"))
      (node (ref "RCLAMP0504FB1") (pin "1") (pinfunction "I1_1") (pintype "bidirectional"))
      (node (ref "U1") (pin "L16") (pinfunction "USB1_DM_L16") (pintype "bidirectional"))
    )
    (net (code "70") (name "Net-(RCLAMP0504FB1-I2)") (class "Default")
      (node (ref "J6") (pin "D+") (pinfunction "D+_D+") (pintype "bidirectional"))
      (node (ref "RCLAMP0504FB1") (pin "3") (pinfunction "I2_3") (pintype "bidirectional"))
      (node (ref "U1") (pin "L15") (pinfunction "USB1_DP_L15") (pintype "bidirectional"))
    )
    (net (code "71") (name "Net-(TP1-1)") (class "Default")
      (node (ref "J1") (pin "PWR") (pinfunction "PWR_PWR") (pintype "bidirectional"))
      (node (ref "TP1") (pin "P$1") (pinfunction "1_P$1") (pintype "bidirectional"))
      (node (ref "U1") (pin "P10") (pinfunction "VIN_AC_P10") (pintype "power_in"))
      (node (ref "U1") (pin "R10") (pinfunction "VIN_AC_R10") (pintype "power_in"))
      (node (ref "U1") (pin "T10") (pinfunction "VIN_AC_T10") (pintype "power_in"))
    )
    (net (code "72") (name "Net-(TP3-1)") (class "Default")
      (node (ref "TP3") (pin "P$1") (pinfunction "1_P$1") (pintype "bidirectional"))
      (node (ref "U1") (pin "P8") (pinfunction "VIN_BAT_P8") (pintype "power_in"))
      (node (ref "U1") (pin "R8") (pinfunction "VIN_BAT_R8") (pintype "power_in"))
      (node (ref "U1") (pin "T8") (pinfunction "VIN_BAT_T8") (pintype "power_in"))
    )
    (net (code "73") (name "Net-(TP4-1)") (class "Default")
      (node (ref "TP4") (pin "P$1") (pinfunction "1_P$1") (pintype "bidirectional"))
      (node (ref "U1") (pin "N7") (pinfunction "PMIC_BAT_SENSE_N7") (pintype "bidirectional"))
    )
    (net (code "74") (name "Net-(TP5-1)") (class "Default")
      (node (ref "TP5") (pin "P$1") (pinfunction "1_P$1") (pintype "bidirectional"))
      (node (ref "U1") (pin "N6") (pinfunction "PMIC_TS_N6") (pintype "bidirectional"))
    )
    (net (code "75") (name "Net-(TP8-1)") (class "Default")
      (node (ref "D1") (pin "A") (pinfunction "A_A") (pintype "passive"))
      (node (ref "TP8") (pin "P$1") (pinfunction "1_P$1") (pintype "bidirectional"))
      (node (ref "U1") (pin "F11") (pinfunction "SYS_VDD2_3P3V_F11") (pintype "power_in"))
      (node (ref "U1") (pin "G11") (pinfunction "SYS_VDD2_3P3V_G11") (pintype "power_in"))
    )
    (net (code "76") (name "Net-(TP9-1)") (class "Default")
      (node (ref "TP9") (pin "P$1") (pinfunction "1_P$1") (pintype "bidirectional"))
      (node (ref "U1") (pin "K11") (pinfunction "SYS_RTC_1P8V_K11") (pintype "power_in"))
      (node (ref "U1") (pin "L11") (pinfunction "SYS_RTC_1P8V_L11") (pintype "power_in"))
    )
    (net (code "77") (name "Net-(TP10-1)") (class "Default")
      (node (ref "TP10") (pin "P$1") (pinfunction "1_P$1") (pintype "bidirectional"))
      (node (ref "U1") (pin "F8") (pinfunction "SYS_VDD3_3P3V_F8") (pintype "power_in"))
      (node (ref "U1") (pin "F9") (pinfunction "VDDSHV4_F9") (pintype "power_in"))
      (node (ref "U1") (pin "G8") (pinfunction "SYS_VDD3_3P3V_G8") (pintype "power_in"))
      (node (ref "U1") (pin "G9") (pinfunction "VDDSHV5_G9") (pintype "power_in"))
      (node (ref "U1") (pin "H7") (pinfunction "SYS_VDD3_3P3V_H7") (pintype "power_in"))
      (node (ref "U1") (pin "H8") (pinfunction "SYS_VDD3_3P3V_H8") (pintype "power_in"))
      (node (ref "U1") (pin "H9") (pinfunction "VDDSHV6_H9") (pintype "power_in"))
      (node (ref "U1") (pin "J7") (pinfunction "SYS_VDD3_3P3V_J7") (pintype "power_in"))
      (node (ref "U1") (pin "J8") (pinfunction "SYS_VDD3_3P3V_J8") (pintype "power_in"))
      (node (ref "U1") (pin "J9") (pinfunction "VDDSHV1_J9") (pintype "power_in"))
      (node (ref "U1") (pin "K8") (pinfunction "SYS_VDD3_3P3V_K8") (pintype "power_in"))
      (node (ref "U1") (pin "K9") (pinfunction "VDDSHV2_K9") (pintype "power_in"))
      (node (ref "U1") (pin "L8") (pinfunction "SYS_VDD3_3P3V_L8") (pintype "power_in"))
      (node (ref "U1") (pin "L9") (pinfunction "VDDSHV3_L9") (pintype "power_in"))
    )
    (net (code "78") (name "Net-(TP11-1)") (class "Default")
      (node (ref "TP11") (pin "P$1") (pinfunction "1_P$1") (pintype "bidirectional"))
      (node (ref "U1") (pin "F10") (pinfunction "SYS_VDD_1P8V_F10") (pintype "power_in"))
      (node (ref "U1") (pin "G10") (pinfunction "SYS_VDD_1P8V_G10") (pintype "power_in"))
      (node (ref "U1") (pin "H10") (pinfunction "SYS_VDD_1P8V_H10") (pintype "power_in"))
      (node (ref "U1") (pin "H11") (pinfunction "SYS_VDD_1P8V_H11") (pintype "power_in"))
      (node (ref "U1") (pin "J10") (pinfunction "SYS_VDD_1P8V_J10") (pintype "power_in"))
      (node (ref "U1") (pin "J11") (pinfunction "SYS_VDD_1P8V_J11") (pintype "power_in"))
      (node (ref "U1") (pin "K10") (pinfunction "SYS_VDD_1P8V_K10") (pintype "power_in"))
      (node (ref "U1") (pin "L10") (pinfunction "SYS_VDD_1P8V_L10") (pintype "power_in"))
    )
    (net (code "79") (name "Net-(TP12-1)") (class "Default")
      (node (ref "TP12") (pin "P$1") (pinfunction "1_P$1") (pintype "bidirectional"))
      (node (ref "U1") (pin "C11") (pinfunction "I2C0_SDA_C11") (pintype "bidirectional"))
      (node (ref "U1") (pin "D11") (pinfunction "PMIC_SDA_D11") (pintype "bidirectional"))
    )
    (net (code "80") (name "Net-(TP13-1)") (class "Default")
      (node (ref "TP13") (pin "P$1") (pinfunction "1_P$1") (pintype "bidirectional"))
      (node (ref "U1") (pin "C10") (pinfunction "I2C0_SCL_C10") (pintype "bidirectional"))
      (node (ref "U1") (pin "D10") (pinfunction "PMIC_SCL_D10") (pintype "bidirectional"))
    )
    (net (code "81") (name "Net-(TP14-1)") (class "Default")
      (node (ref "TP14") (pin "P$1") (pinfunction "1_P$1") (pintype "bidirectional"))
      (node (ref "U1") (pin "D4") (pinfunction "EXTINTN_D4") (pintype "bidirectional"))
      (node (ref "U1") (pin "E4") (pinfunction "PMIC_NINT_E4") (pintype "output"))
    )
    (net (code "82") (name "Net-(TP15-1)") (class "Default")
      (node (ref "TP15") (pin "P$1") (pinfunction "1_P$1") (pintype "bidirectional"))
      (node (ref "U1") (pin "L4") (pinfunction "PMIC_NWAKEUP_L4") (pintype "output"))
      (node (ref "U1") (pin "M4") (pinfunction "EXT_WAKEUP_M4") (pintype "bidirectional"))
    )
    (net (code "83") (name "Net-(TP16-1)") (class "Default")
      (node (ref "TP16") (pin "P$1") (pinfunction "1_P$1") (pintype "bidirectional"))
      (node (ref "U1") (pin "N4") (pinfunction "PMIC_LDO_PGOOD_N4") (pintype "output"))
      (node (ref "U1") (pin "N5") (pinfunction "RTC_PWRONRSTN_N5") (pintype "bidirectional"))
    )
    (net (code "84") (name "Net-(TP17-1)") (class "Default")
      (node (ref "TP17") (pin "P$1") (pinfunction "1_P$1") (pintype "bidirectional"))
      (node (ref "U1") (pin "N10") (pinfunction "PMIC_POWER_EN_N10") (pintype "output"))
      (node (ref "U1") (pin "N11") (pinfunction "PMIC_PWR_EN_N11") (pintype "input"))
    )
    (net (code "85") (name "Net-(TP18-1)") (class "Default")
      (node (ref "TP18") (pin "P$1") (pinfunction "1_P$1") (pintype "bidirectional"))
      (node (ref "U1") (pin "M13") (pinfunction "PMIC_NRESET_M13") (pintype "bidirectional"))
    )
    (net (code "86") (name "Net-(TP19-1)") (class "Default")
      (node (ref "C1") (pin "1") (pinfunction "1_1") (pintype "passive"))
      (node (ref "TP19") (pin "P$1") (pinfunction "1_P$1") (pintype "bidirectional"))
      (node (ref "U2") (pin "5") (pinfunction "VCC_5") (pintype "bidirectional"))
    )
    (net (code "87") (name "Net-(TP21-1)") (class "Default")
      (node (ref "TP21") (pin "P$1") (pinfunction "1_P$1") (pintype "bidirectional"))
      (node (ref "U1") (pin "E2") (pinfunction "EMU0_E2") (pintype "bidirectional"))
    )
    (net (code "88") (name "Net-(TP22-1)") (class "Default")
      (node (ref "TP22") (pin "P$1") (pinfunction "1_P$1") (pintype "bidirectional"))
      (node (ref "U1") (pin "E3") (pinfunction "EMU1_E3") (pintype "bidirectional"))
    )
    (net (code "89") (name "Net-(U1A-EEPROM_WP)") (class "Default")
      (node (ref "TP20") (pin "1") (pinfunction "1_1") (pintype "bidirectional"))
      (node (ref "U1") (pin "M2") (pinfunction "EEPROM_WP_M2") (pintype "bidirectional"))
    )
    (net (code "90") (name "Net-(U1A-PMIC_PB_IN)") (class "Default")
      (node (ref "S1") (pin "3") (pinfunction "2_3") (pintype "passive"))
      (node (ref "S1") (pin "4") (pinfunction "2_4") (pintype "passive"))
      (node (ref "U1") (pin "T11") (pinfunction "PMIC_PB_IN_T11") (pintype "bidirectional"))
    )
    (net (code "91") (name "Net-(U1A-RTC_KALDO_ENN)") (class "Default")
      (node (ref "R19") (pin "2") (pinfunction "2_2") (pintype "passive"))
      (node (ref "U1") (pin "M16") (pinfunction "RTC_KALDO_ENN_M16") (pintype "bidirectional"))
    )
    (net (code "92") (name "Net-(U1B-USB1_DRVVBUS)") (class "Default")
      (node (ref "R20") (pin "2") (pinfunction "2_2") (pintype "passive"))
      (node (ref "U1") (pin "M14") (pinfunction "USB1_DRVVBUS_M14") (pintype "bidirectional"))
      (node (ref "U3") (pin "4") (pinfunction "EN_4") (pintype "input"))
    )
    (net (code "93") (name "Net-(U1B-USB1_VBUS)") (class "Default")
      (node (ref "FB3") (pin "1") (pinfunction "1_1") (pintype "passive"))
      (node (ref "U1") (pin "M15") (pinfunction "USB1_VBUS_M15") (pintype "bidirectional"))
    )
    (net (code "94") (name "Net-(U1C-GPMC_A4)") (class "Default")
      (node (ref "U1") (pin "R13") (pinfunction "GPMC_A4_R13") (pintype "bidirectional"))
      (node (ref "U4") (pin "K5") (pinfunction "~{RST}_K5") (pintype "input"))
    )
    (net (code "95") (name "Net-(U1C-GPMC_A5)") (class "Default")
      (node (ref "D2") (pin "A") (pinfunction "A_A") (pintype "passive"))
      (node (ref "U1") (pin "P13") (pinfunction "GPMC_A5_P13") (pintype "bidirectional"))
    )
    (net (code "96") (name "Net-(U1C-GPMC_A6)") (class "Default")
      (node (ref "D3") (pin "A") (pinfunction "A_A") (pintype "passive"))
      (node (ref "U1") (pin "T14") (pinfunction "GPMC_A6_T14") (pintype "bidirectional"))
    )
    (net (code "97") (name "Net-(U1C-GPMC_A7)") (class "Default")
      (node (ref "D4") (pin "A") (pinfunction "A_A") (pintype "passive"))
      (node (ref "U1") (pin "R14") (pinfunction "GPMC_A7_R14") (pintype "bidirectional"))
    )
    (net (code "98") (name "Net-(U1C-GPMC_A8)") (class "Default")
      (node (ref "D5") (pin "A") (pinfunction "A_A") (pintype "passive"))
      (node (ref "U1") (pin "P14") (pinfunction "GPMC_A8_P14") (pintype "bidirectional"))
    )
    (net (code "99") (name "Net-(U1C-GPMC_AD0)") (class "Default")
      (node (ref "U1") (pin "R3") (pinfunction "GPMC_AD0_R3") (pintype "bidirectional"))
      (node (ref "U4") (pin "A3") (pinfunction "D0_A3") (pintype "input"))
    )
    (net (code "100") (name "Net-(U1C-GPMC_AD1)") (class "Default")
      (node (ref "U1") (pin "R2") (pinfunction "GPMC_AD1_R2") (pintype "bidirectional"))
      (node (ref "U4") (pin "A4") (pinfunction "D1_A4") (pintype "input"))
    )
    (net (code "101") (name "Net-(U1C-GPMC_AD2)") (class "Default")
      (node (ref "U1") (pin "R1") (pinfunction "GPMC_AD2_R1") (pintype "bidirectional"))
      (node (ref "U4") (pin "A5") (pinfunction "D2_A5") (pintype "input"))
    )
    (net (code "102") (name "Net-(U1C-GPMC_AD3)") (class "Default")
      (node (ref "U1") (pin "T3") (pinfunction "GPMC_AD3_T3") (pintype "bidirectional"))
      (node (ref "U4") (pin "B2") (pinfunction "D3_B2") (pintype "input"))
    )
    (net (code "103") (name "Net-(U1C-GPMC_AD4)") (class "Default")
      (node (ref "U1") (pin "T2") (pinfunction "GPMC_AD4_T2") (pintype "bidirectional"))
      (node (ref "U4") (pin "B3") (pinfunction "D4_B3") (pintype "input"))
    )
    (net (code "104") (name "Net-(U1C-GPMC_AD5)") (class "Default")
      (node (ref "U1") (pin "T1") (pinfunction "GPMC_AD5_T1") (pintype "bidirectional"))
      (node (ref "U4") (pin "B4") (pinfunction "D5_B4") (pintype "input"))
    )
    (net (code "105") (name "Net-(U1C-GPMC_AD6)") (class "Default")
      (node (ref "U1") (pin "P4") (pinfunction "GPMC_AD6_P4") (pintype "bidirectional"))
      (node (ref "U4") (pin "B5") (pinfunction "D6_B5") (pintype "bidirectional"))
    )
    (net (code "106") (name "Net-(U1C-GPMC_AD7)") (class "Default")
      (node (ref "U1") (pin "R4") (pinfunction "GPMC_AD7_R4") (pintype "bidirectional"))
      (node (ref "U4") (pin "B6") (pinfunction "D7_B6") (pintype "input"))
    )
    (net (code "107") (name "Net-(U1C-GPMC_CSN1)") (class "Default")
      (node (ref "R8") (pin "1") (pinfunction "1_1") (pintype "passive"))
      (node (ref "U1") (pin "P2") (pinfunction "GPMC_CSN1_P2") (pintype "bidirectional"))
    )
    (net (code "108") (name "Net-(U1C-GPMC_CSN2)") (class "Default")
      (node (ref "U1") (pin "P1") (pinfunction "GPMC_CSN2_P1") (pintype "bidirectional"))
      (node (ref "U4") (pin "M5") (pinfunction "CMD_M5") (pintype "input"))
    )
    (net (code "109") (name "Net-(U1D-LCD_DATA0)") (class "Default")
      (node (ref "J3") (pin "1") (pinfunction "1_1") (pintype "passive"))
      (node (ref "U1") (pin "G3") (pinfunction "LCD_DATA0_G3") (pintype "bidirectional"))
    )
    (net (code "110") (name "Net-(U1D-LCD_DATA1)") (class "Default")
      (node (ref "J3") (pin "2") (pinfunction "2_2") (pintype "passive"))
      (node (ref "U1") (pin "G2") (pinfunction "LCD_DATA1_G2") (pintype "bidirectional"))
    )
    (net (code "111") (name "Net-(U1D-LCD_DATA2)") (class "Default")
      (node (ref "J3") (pin "3") (pinfunction "3_3") (pintype "passive"))
      (node (ref "U1") (pin "G1") (pinfunction "LCD_DATA2_G1") (pintype "bidirectional"))
    )
    (net (code "112") (name "Net-(U1D-LCD_DATA3)") (class "Default")
      (node (ref "J3") (pin "4") (pinfunction "4_4") (pintype "passive"))
      (node (ref "U1") (pin "H3") (pinfunction "LCD_DATA3_H3") (pintype "bidirectional"))
    )
    (net (code "113") (name "Net-(U1D-LCD_DATA4)") (class "Default")
      (node (ref "J3") (pin "5") (pinfunction "5_5") (pintype "passive"))
      (node (ref "U1") (pin "H2") (pinfunction "LCD_DATA4_H2") (pintype "bidirectional"))
    )
    (net (code "114") (name "Net-(U3-~{FLT})") (class "Default")
      (node (ref "R21") (pin "1") (pinfunction "1_1") (pintype "passive"))
      (node (ref "U3") (pin "3") (pinfunction "~{FLT}_3") (pintype "output"))
    )
    (net (code "115") (name "Net-(U4-SCK)") (class "Default")
      (node (ref "R8") (pin "2") (pinfunction "2_2") (pintype "passive"))
      (node (ref "U4") (pin "M6") (pinfunction "SCK_M6") (pintype "input"))
    )
    (net (code "116") (name "Net-(U4-VDDI)") (class "Default")
      (node (ref "C14") (pin "1") (pinfunction "1_1") (pintype "passive"))
      (node (ref "U4") (pin "C2") (pinfunction "VDDI_C2") (pintype "power_in"))
    )
    (net (code "117") (name "PIXCLK") (class "Default")
      (node (ref "U1") (pin "B4") (pinfunction "XDMA_EVENT_INTR1_B4") (pintype "bidirectional"))
    )
    (net (code "118") (name "VDD") (class "Default")
      (node (ref "C10") (pin "1") (pinfunction "1_1") (pintype "passive"))
      (node (ref "R21") (pin "2") (pinfunction "2_2") (pintype "passive"))
      (node (ref "TP6") (pin "P$1") (pinfunction "1_P$1") (pintype "bidirectional"))
      (node (ref "U1") (pin "K6") (pinfunction "SYS_VOUT_K6") (pintype "power_in"))
      (node (ref "U1") (pin "K7") (pinfunction "SYS_VOUT_K7") (pintype "power_in"))
      (node (ref "U1") (pin "L6") (pinfunction "SYS_VOUT_L6") (pintype "power_in"))
      (node (ref "U1") (pin "L7") (pinfunction "SYS_VOUT_L7") (pintype "power_in"))
      (node (ref "U3") (pin "5") (pinfunction "IN_5") (pintype "input"))
    )
    (net (code "119") (name "VIN_USB") (class "Default")
      (node (ref "C11") (pin "1") (pinfunction "1_1") (pintype "passive"))
      (node (ref "C6") (pin "1") (pinfunction "1_1") (pintype "passive"))
      (node (ref "C8") (pin "1") (pinfunction "1_1") (pintype "passive"))
      (node (ref "FB1") (pin "2") (pinfunction "2_2") (pintype "passive"))
      (node (ref "FB2") (pin "1") (pinfunction "1_1") (pintype "passive"))
      (node (ref "FB3") (pin "2") (pinfunction "2_2") (pintype "passive"))
      (node (ref "RCLAMP0504FB") (pin "5") (pinfunction "VCC_5") (pintype "power_in"))
      (node (ref "RCLAMP0504FB1") (pin "5") (pinfunction "VCC_5") (pintype "power_in"))
      (node (ref "TP2") (pin "P$1") (pinfunction "1_P$1") (pintype "bidirectional"))
      (node (ref "U1") (pin "J16") (pinfunction "USB0_VBUS_J16") (pintype "bidirectional"))
      (node (ref "U1") (pin "P9") (pinfunction "VIN_USB_P9") (pintype "power_in"))
      (node (ref "U1") (pin "R9") (pinfunction "VIN_USB_R9") (pintype "power_in"))
      (node (ref "U1") (pin "T9") (pinfunction "VIN_USB_T9") (pintype "power_in"))
      (node (ref "U3") (pin "1") (pinfunction "OUT_1") (pintype "output"))
    )
    (net (code "120") (name "VSYNC") (class "Default")
      (node (ref "U1") (pin "T6") (pinfunction "GPMC_AD14_T6") (pintype "bidirectional"))
    )
    (net (code "121") (name "unconnected-(R4-11-Pad1)") (class "Default")
      (node (ref "R4") (pin "1") (pinfunction "11_1") (pintype "passive"))
    )
    (net (code "122") (name "unconnected-(R5-11-Pad1)") (class "Default")
      (node (ref "R5") (pin "1") (pinfunction "11_1") (pintype "passive"))
    )
    (net (code "123") (name "unconnected-(R5-99-Pad9)") (class "Default")
      (node (ref "R5") (pin "9") (pinfunction "99_9") (pintype "passive"))
    )
    (net (code "124") (name "unconnected-(R7-11-Pad1)") (class "Default")
      (node (ref "R7") (pin "1") (pinfunction "11_1") (pintype "passive"))
    )
    (net (code "125") (name "unconnected-(RCLAMP0504FB-I4-Pad6)") (class "Default")
      (node (ref "RCLAMP0504FB") (pin "6") (pinfunction "I4_6") (pintype "bidirectional"))
    )
    (net (code "126") (name "unconnected-(RCLAMP0504FB1-I3-Pad4)") (class "Default")
      (node (ref "RCLAMP0504FB1") (pin "4") (pinfunction "I3_4") (pintype "bidirectional"))
    )
    (net (code "127") (name "unconnected-(RCLAMP0504FB1-I4-Pad6)") (class "Default")
      (node (ref "RCLAMP0504FB1") (pin "6") (pinfunction "I4_6") (pintype "bidirectional"))
    )
    (net (code "128") (name "unconnected-(U1B-AIN0-PadA8)") (class "Default")
      (node (ref "U1") (pin "A8") (pinfunction "AIN0_A8") (pintype "bidirectional"))
    )
    (net (code "129") (name "unconnected-(U1B-AIN1-PadB8)") (class "Default")
      (node (ref "U1") (pin "B8") (pinfunction "AIN1_B8") (pintype "bidirectional"))
    )
    (net (code "130") (name "unconnected-(U1B-AIN2-PadB6)") (class "Default")
      (node (ref "U1") (pin "B6") (pinfunction "AIN2_B6") (pintype "bidirectional"))
    )
    (net (code "131") (name "unconnected-(U1B-AIN3-PadC6)") (class "Default")
      (node (ref "U1") (pin "C6") (pinfunction "AIN3_C6") (pintype "bidirectional"))
    )
    (net (code "132") (name "unconnected-(U1B-AIN4-PadC7)") (class "Default")
      (node (ref "U1") (pin "C7") (pinfunction "AIN4_C7") (pintype "bidirectional"))
    )
    (net (code "133") (name "unconnected-(U1B-AIN5-PadC8)") (class "Default")
      (node (ref "U1") (pin "C8") (pinfunction "AIN5_C8") (pintype "bidirectional"))
    )
    (net (code "134") (name "unconnected-(U1B-AIN6-PadC9)") (class "Default")
      (node (ref "U1") (pin "C9") (pinfunction "AIN6_C9") (pintype "bidirectional"))
    )
    (net (code "135") (name "unconnected-(U1B-AIN7-PadD7)") (class "Default")
      (node (ref "U1") (pin "D7") (pinfunction "AIN7_D7") (pintype "bidirectional"))
    )
    (net (code "136") (name "unconnected-(U1B-PMIC_MUX_IN-PadN13)") (class "Default")
      (node (ref "U1") (pin "N13") (pinfunction "PMIC_MUX_IN_N13") (pintype "bidirectional"))
    )
    (net (code "137") (name "unconnected-(U1B-PMIC_MUX_OUT-PadD6)") (class "Default")
      (node (ref "U1") (pin "D6") (pinfunction "PMIC_MUX_OUT_D6") (pintype "bidirectional"))
    )
    (net (code "138") (name "unconnected-(U1B-USB0_CE-PadK13)") (class "Default")
      (node (ref "U1") (pin "K13") (pinfunction "USB0_CE_K13") (pintype "bidirectional"))
    )
    (net (code "139") (name "unconnected-(U1B-USB0_DRVVBUS-PadJ15)") (class "Default")
      (node (ref "U1") (pin "J15") (pinfunction "USB0_DRVVBUS_J15") (pintype "bidirectional"))
    )
    (net (code "140") (name "unconnected-(U1B-USB1_CE-PadL13)") (class "Default")
      (node (ref "U1") (pin "L13") (pinfunction "USB1_CE_L13") (pintype "bidirectional"))
    )
    (net (code "141") (name "unconnected-(U1C-ECAP0_IN_PWM0_OUT-PadC5)") (class "Default")
      (node (ref "U1") (pin "C5") (pinfunction "ECAP0_IN_PWM0_OUT_C5") (pintype "bidirectional"))
    )
    (net (code "142") (name "unconnected-(U1C-GPMC_A0-PadT12)") (class "Default")
      (node (ref "U1") (pin "T12") (pinfunction "GPMC_A0_T12") (pintype "bidirectional"))
    )
    (net (code "143") (name "unconnected-(U1C-GPMC_A1-PadR12)") (class "Default")
      (node (ref "U1") (pin "R12") (pinfunction "GPMC_A1_R12") (pintype "bidirectional"))
    )
    (net (code "144") (name "unconnected-(U1C-GPMC_A2-PadP12)") (class "Default")
      (node (ref "U1") (pin "P12") (pinfunction "GPMC_A2_P12") (pintype "bidirectional"))
    )
    (net (code "145") (name "unconnected-(U1C-GPMC_A3-PadT13)") (class "Default")
      (node (ref "U1") (pin "T13") (pinfunction "GPMC_A3_T13") (pintype "bidirectional"))
    )
    (net (code "146") (name "unconnected-(U1C-GPMC_A9-PadT15)") (class "Default")
      (node (ref "U1") (pin "T15") (pinfunction "GPMC_A9_T15") (pintype "bidirectional"))
    )
    (net (code "147") (name "unconnected-(U1C-GPMC_A10-PadR15)") (class "Default")
      (node (ref "U1") (pin "R15") (pinfunction "GPMC_A10_R15") (pintype "bidirectional"))
    )
    (net (code "148") (name "unconnected-(U1C-GPMC_A11-PadT16)") (class "Default")
      (node (ref "U1") (pin "T16") (pinfunction "GPMC_A11_T16") (pintype "bidirectional"))
    )
    (net (code "149") (name "unconnected-(U1C-GPMC_AD8-PadT4)") (class "Default")
      (node (ref "U1") (pin "T4") (pinfunction "GPMC_AD8_T4") (pintype "bidirectional"))
    )
    (net (code "150") (name "unconnected-(U1C-GPMC_AD9-PadP5)") (class "Default")
      (node (ref "U1") (pin "P5") (pinfunction "GPMC_AD9_P5") (pintype "bidirectional"))
    )
    (net (code "151") (name "unconnected-(U1C-GPMC_AD10-PadR5)") (class "Default")
      (node (ref "U1") (pin "R5") (pinfunction "GPMC_AD10_R5") (pintype "bidirectional"))
    )
    (net (code "152") (name "unconnected-(U1C-GPMC_AD11-PadT5)") (class "Default")
      (node (ref "U1") (pin "T5") (pinfunction "GPMC_AD11_T5") (pintype "bidirectional"))
    )
    (net (code "153") (name "unconnected-(U1C-GPMC_AD12-PadP6)") (class "Default")
      (node (ref "U1") (pin "P6") (pinfunction "GPMC_AD12_P6") (pintype "bidirectional"))
    )
    (net (code "154") (name "unconnected-(U1C-GPMC_AD13-PadR6)") (class "Default")
      (node (ref "U1") (pin "R6") (pinfunction "GPMC_AD13_R6") (pintype "bidirectional"))
    )
    (net (code "155") (name "unconnected-(U1C-GPMC_ADVN_ALE-PadM1)") (class "Default")
      (node (ref "U1") (pin "M1") (pinfunction "GPMC_ADVN_ALE_M1") (pintype "bidirectional"))
    )
    (net (code "156") (name "unconnected-(U1C-GPMC_BEN0_CLE-PadN3)") (class "Default")
      (node (ref "U1") (pin "N3") (pinfunction "GPMC_BEN0_CLE_N3") (pintype "bidirectional"))
    )
    (net (code "157") (name "unconnected-(U1C-GPMC_BEN1-PadN14)") (class "Default")
      (node (ref "U1") (pin "N14") (pinfunction "GPMC_BEN1_N14") (pintype "bidirectional"))
    )
    (net (code "158") (name "unconnected-(U1C-GPMC_CLK-PadT7)") (class "Default")
      (node (ref "U1") (pin "T7") (pinfunction "GPMC_CLK_T7") (pintype "bidirectional"))
    )
    (net (code "159") (name "unconnected-(U1C-GPMC_CSN0-PadP3)") (class "Default")
      (node (ref "U1") (pin "P3") (pinfunction "GPMC_CSN0_P3") (pintype "bidirectional"))
    )
    (net (code "160") (name "unconnected-(U1C-GPMC_CSN3-PadR7)") (class "Default")
      (node (ref "U1") (pin "R7") (pinfunction "GPMC_CSN3_R7") (pintype "bidirectional"))
    )
    (net (code "161") (name "unconnected-(U1C-GPMC_OEN_REN-PadN1)") (class "Default")
      (node (ref "U1") (pin "N1") (pinfunction "GPMC_OEN_REN_N1") (pintype "bidirectional"))
    )
    (net (code "162") (name "unconnected-(U1C-GPMC_WAIT0-PadP15)") (class "Default")
      (node (ref "U1") (pin "P15") (pinfunction "GPMC_WAIT0_P15") (pintype "bidirectional"))
    )
    (net (code "163") (name "unconnected-(U1C-GPMC_WEN-PadN2)") (class "Default")
      (node (ref "U1") (pin "N2") (pinfunction "GPMC_WEN_N2") (pintype "bidirectional"))
    )
    (net (code "164") (name "unconnected-(U1C-GPMC_WPN-PadR16)") (class "Default")
      (node (ref "U1") (pin "R16") (pinfunction "GPMC_WPN_R16") (pintype "bidirectional"))
    )
    (net (code "165") (name "unconnected-(U1C-SPI0_CS0-PadA14)") (class "Default")
      (node (ref "U1") (pin "A14") (pinfunction "SPI0_CS0_A14") (pintype "bidirectional"))
    )
    (net (code "166") (name "unconnected-(U1C-SPI0_D0-PadB13)") (class "Default")
      (node (ref "U1") (pin "B13") (pinfunction "SPI0_D0_B13") (pintype "bidirectional"))
    )
    (net (code "167") (name "unconnected-(U1C-SPI0_D1-PadB14)") (class "Default")
      (node (ref "U1") (pin "B14") (pinfunction "SPI0_D1_B14") (pintype "bidirectional"))
    )
    (net (code "168") (name "unconnected-(U1C-SPI0_SCLK-PadA13)") (class "Default")
      (node (ref "U1") (pin "A13") (pinfunction "SPI0_SCLK_A13") (pintype "bidirectional"))
    )
    (net (code "169") (name "unconnected-(U1C-UART0_CTSN-PadC12)") (class "Default")
      (node (ref "U1") (pin "C12") (pinfunction "UART0_CTSN_C12") (pintype "bidirectional"))
    )
    (net (code "170") (name "unconnected-(U1C-UART0_RTSN-PadC13)") (class "Default")
      (node (ref "U1") (pin "C13") (pinfunction "UART0_RTSN_C13") (pintype "bidirectional"))
    )
    (net (code "171") (name "unconnected-(U1C-UART0_RXD-PadA12)") (class "Default")
      (node (ref "U1") (pin "A12") (pinfunction "UART0_RXD_A12") (pintype "bidirectional"))
    )
    (net (code "172") (name "unconnected-(U1C-UART0_TXD-PadB12)") (class "Default")
      (node (ref "U1") (pin "B12") (pinfunction "UART0_TXD_B12") (pintype "bidirectional"))
    )
    (net (code "173") (name "unconnected-(U1C-UART1_CTSN-PadB10)") (class "Default")
      (node (ref "U1") (pin "B10") (pinfunction "UART1_CTSN_B10") (pintype "bidirectional"))
    )
    (net (code "174") (name "unconnected-(U1C-UART1_RTSN-PadA10)") (class "Default")
      (node (ref "U1") (pin "A10") (pinfunction "UART1_RTSN_A10") (pintype "bidirectional"))
    )
    (net (code "175") (name "unconnected-(U1C-UART1_RXD-PadA11)") (class "Default")
      (node (ref "U1") (pin "A11") (pinfunction "UART1_RXD_A11") (pintype "bidirectional"))
    )
    (net (code "176") (name "unconnected-(U1C-UART1_TXD-PadB11)") (class "Default")
      (node (ref "U1") (pin "B11") (pinfunction "UART1_TXD_B11") (pintype "bidirectional"))
    )
    (net (code "177") (name "unconnected-(U1C-XDMA_EVENT_INTR0-PadA4)") (class "Default")
      (node (ref "U1") (pin "A4") (pinfunction "XDMA_EVENT_INTR0_A4") (pintype "bidirectional"))
    )
    (net (code "178") (name "unconnected-(U1D-LCD_AC_BIAS_EN-PadE1)") (class "Default")
      (node (ref "U1") (pin "E1") (pinfunction "LCD_AC_BIAS_EN_E1") (pintype "bidirectional"))
    )
    (net (code "179") (name "unconnected-(U1D-LCD_HSYNC-PadF2)") (class "Default")
      (node (ref "U1") (pin "F2") (pinfunction "LCD_HSYNC_F2") (pintype "bidirectional"))
    )
    (net (code "180") (name "unconnected-(U1D-LCD_PCLK-PadF1)") (class "Default")
      (node (ref "U1") (pin "F1") (pinfunction "LCD_PCLK_F1") (pintype "bidirectional"))
    )
    (net (code "181") (name "unconnected-(U1D-LCD_VSYNC-PadF3)") (class "Default")
      (node (ref "U1") (pin "F3") (pinfunction "LCD_VSYNC_F3") (pintype "bidirectional"))
    )
    (net (code "182") (name "unconnected-(U1D-MDC-PadD13)") (class "Default")
      (node (ref "U1") (pin "D13") (pinfunction "MDC_D13") (pintype "bidirectional"))
    )
    (net (code "183") (name "unconnected-(U1D-MDIO-PadE13)") (class "Default")
      (node (ref "U1") (pin "E13") (pinfunction "MDIO_E13") (pintype "bidirectional"))
    )
    (net (code "184") (name "unconnected-(U1D-MII1_COL-PadF15)") (class "Default")
      (node (ref "U1") (pin "F15") (pinfunction "MII1_COL_F15") (pintype "bidirectional"))
    )
    (net (code "185") (name "unconnected-(U1D-MII1_CRS-PadF14)") (class "Default")
      (node (ref "U1") (pin "F14") (pinfunction "MII1_CRS_F14") (pintype "bidirectional"))
    )
    (net (code "186") (name "unconnected-(U1D-MII1_RXD0-PadE14)") (class "Default")
      (node (ref "U1") (pin "E14") (pinfunction "MII1_RXD0_E14") (pintype "bidirectional"))
    )
    (net (code "187") (name "unconnected-(U1D-MII1_RXD1-PadD16)") (class "Default")
      (node (ref "U1") (pin "D16") (pinfunction "MII1_RXD1_D16") (pintype "bidirectional"))
    )
    (net (code "188") (name "unconnected-(U1D-MII1_RXD2-PadD15)") (class "Default")
      (node (ref "U1") (pin "D15") (pinfunction "MII1_RXD2_D15") (pintype "bidirectional"))
    )
    (net (code "189") (name "unconnected-(U1D-MII1_RXD3-PadD14)") (class "Default")
      (node (ref "U1") (pin "D14") (pinfunction "MII1_RXD3_D14") (pintype "bidirectional"))
    )
    (net (code "190") (name "unconnected-(U1D-MII1_RX_CLK-PadE16)") (class "Default")
      (node (ref "U1") (pin "E16") (pinfunction "MII1_RX_CLK_E16") (pintype "bidirectional"))
    )
    (net (code "191") (name "unconnected-(U1D-MII1_RX_DV-PadF16)") (class "Default")
      (node (ref "U1") (pin "F16") (pinfunction "MII1_RX_DV_F16") (pintype "bidirectional"))
    )
    (net (code "192") (name "unconnected-(U1D-MII1_RX_ER-PadE15)") (class "Default")
      (node (ref "U1") (pin "E15") (pinfunction "MII1_RX_ER_E15") (pintype "bidirectional"))
    )
    (net (code "193") (name "unconnected-(U1D-MII1_TXD0-PadH15)") (class "Default")
      (node (ref "U1") (pin "H15") (pinfunction "MII1_TXD0_H15") (pintype "bidirectional"))
    )
    (net (code "194") (name "unconnected-(U1D-MII1_TXD1-PadH14)") (class "Default")
      (node (ref "U1") (pin "H14") (pinfunction "MII1_TXD1_H14") (pintype "bidirectional"))
    )
    (net (code "195") (name "unconnected-(U1D-MII1_TXD2-PadG16)") (class "Default")
      (node (ref "U1") (pin "G16") (pinfunction "MII1_TXD2_G16") (pintype "bidirectional"))
    )
    (net (code "196") (name "unconnected-(U1D-MII1_TXD3-PadG15)") (class "Default")
      (node (ref "U1") (pin "G15") (pinfunction "MII1_TXD3_G15") (pintype "bidirectional"))
    )
    (net (code "197") (name "unconnected-(U1D-MII1_TX_CLK-PadH16)") (class "Default")
      (node (ref "U1") (pin "H16") (pinfunction "MII1_TX_CLK_H16") (pintype "bidirectional"))
    )
    (net (code "198") (name "unconnected-(U1D-MII1_TX_EN-PadG14)") (class "Default")
      (node (ref "U1") (pin "G14") (pinfunction "MII1_TX_EN_G14") (pintype "bidirectional"))
    )
    (net (code "199") (name "unconnected-(U1D-RMII1_REF_CLK-PadJ14)") (class "Default")
      (node (ref "U1") (pin "J14") (pinfunction "RMII1_REF_CLK_J14") (pintype "bidirectional"))
    )
    (net (code "200") (name "unconnected-(U1F-CAP_VDD_RTC-PadD5)") (class "Default")
      (node (ref "U1") (pin "D5") (pinfunction "CAP_VDD_RTC_D5") (pintype "bidirectional"))
    )
    (net (code "201") (name "unconnected-(U1F-NC-PadD12)") (class "Default")
      (node (ref "U1") (pin "D12") (pinfunction "NC_D12") (pintype "bidirectional"))
    )
    (net (code "202") (name "unconnected-(U1F-NC-PadJ6)") (class "Default")
      (node (ref "U1") (pin "J6") (pinfunction "NC_J6") (pintype "bidirectional"))
    )
    (net (code "203") (name "unconnected-(U1F-NC-PadK4)") (class "Default")
      (node (ref "U1") (pin "K4") (pinfunction "NC_K4") (pintype "bidirectional"))
    )
    (net (code "204") (name "unconnected-(U1F-VDDS_DDR-PadF4)") (class "Default")
      (node (ref "U1") (pin "F4") (pinfunction "VDDS_DDR_F4") (pintype "bidirectional"))
    )
    (net (code "205") (name "unconnected-(U1F-VDDS_PLL-PadG13)") (class "Default")
      (node (ref "U1") (pin "G13") (pinfunction "VDDS_PLL_G13") (pintype "bidirectional"))
    )
    (net (code "206") (name "unconnected-(U1F-VDD_CORE-PadG4)") (class "Default")
      (node (ref "U1") (pin "G4") (pinfunction "VDD_CORE_G4") (pintype "bidirectional"))
    )
    (net (code "207") (name "unconnected-(U1F-VDD_MPU-PadF13)") (class "Default")
      (node (ref "U1") (pin "F13") (pinfunction "VDD_MPU_F13") (pintype "bidirectional"))
    )
    (net (code "208") (name "unconnected-(U1F-VPP-PadH6)") (class "Default")
      (node (ref "U1") (pin "H6") (pinfunction "VPP_H6") (pintype "bidirectional"))
    )
  )
)
